# Digitizer.net
KiCad netlist of a schematic drawn in Altium Designer
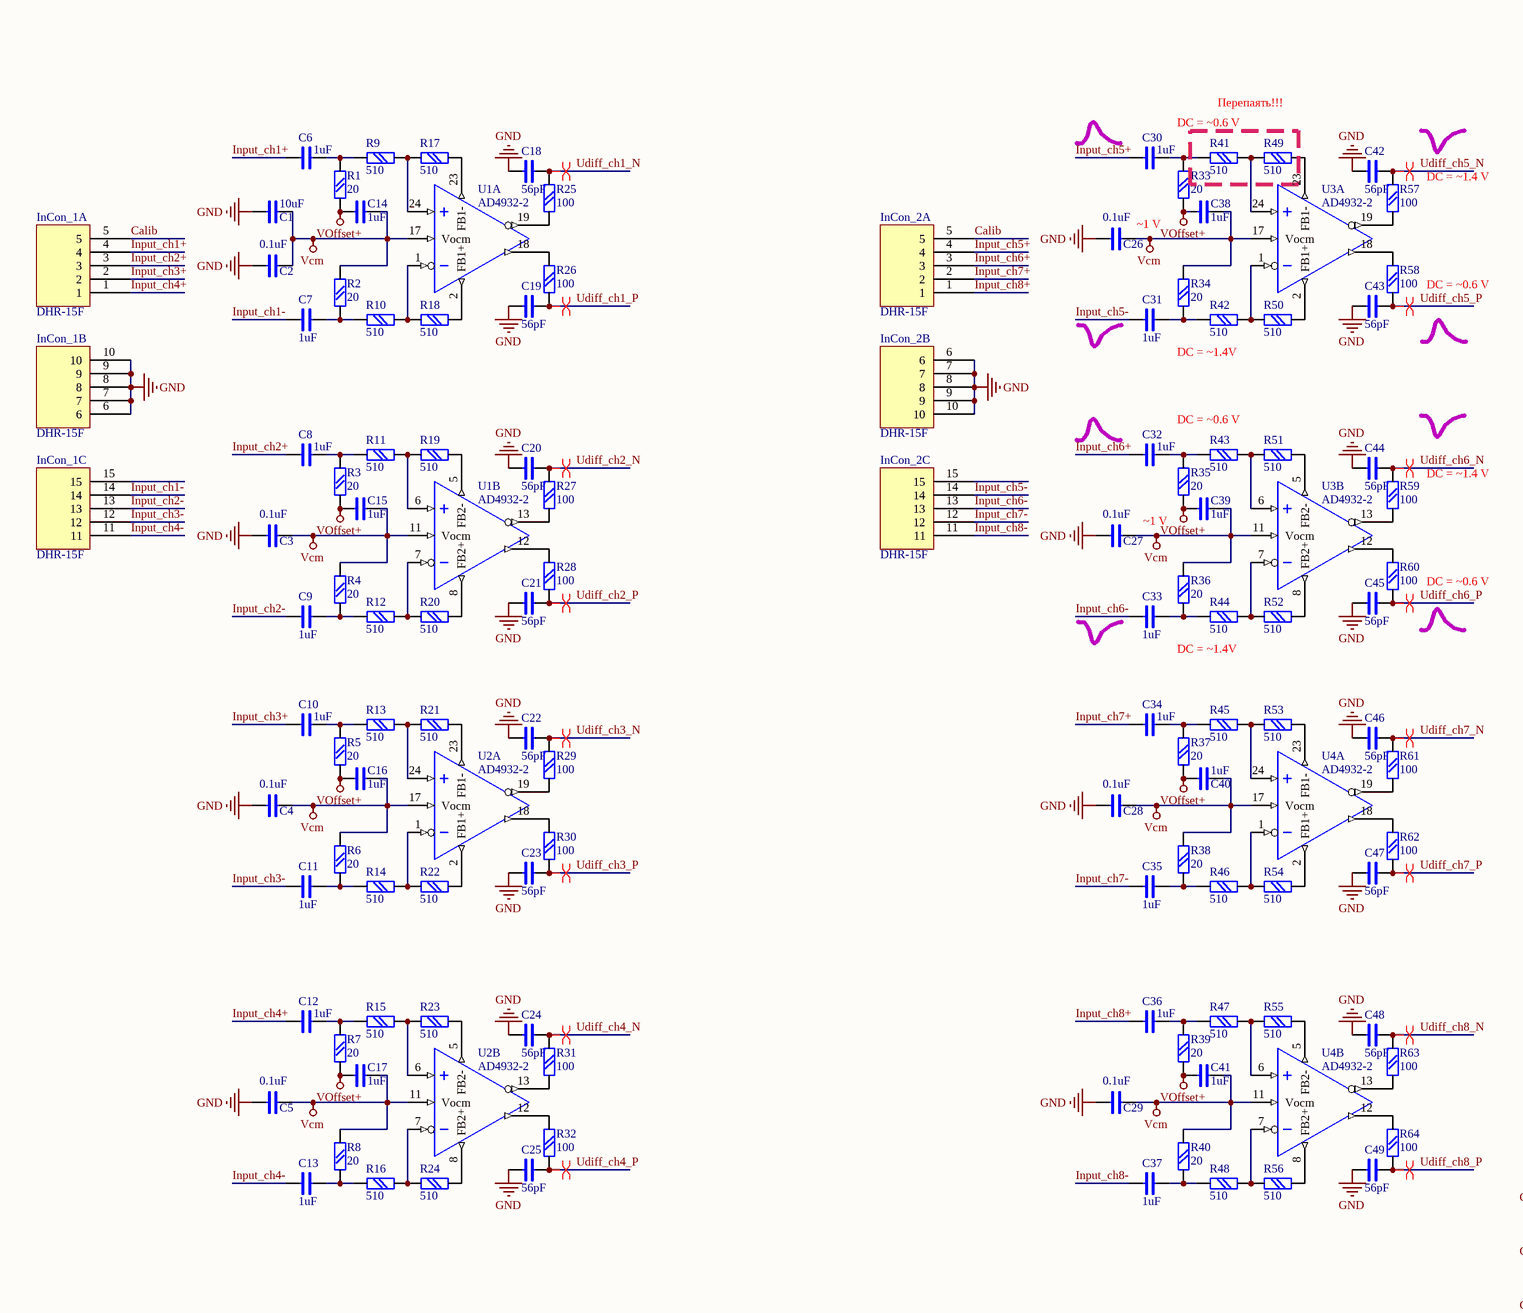
[diagram p0: Digitizer.SchDoc, left]
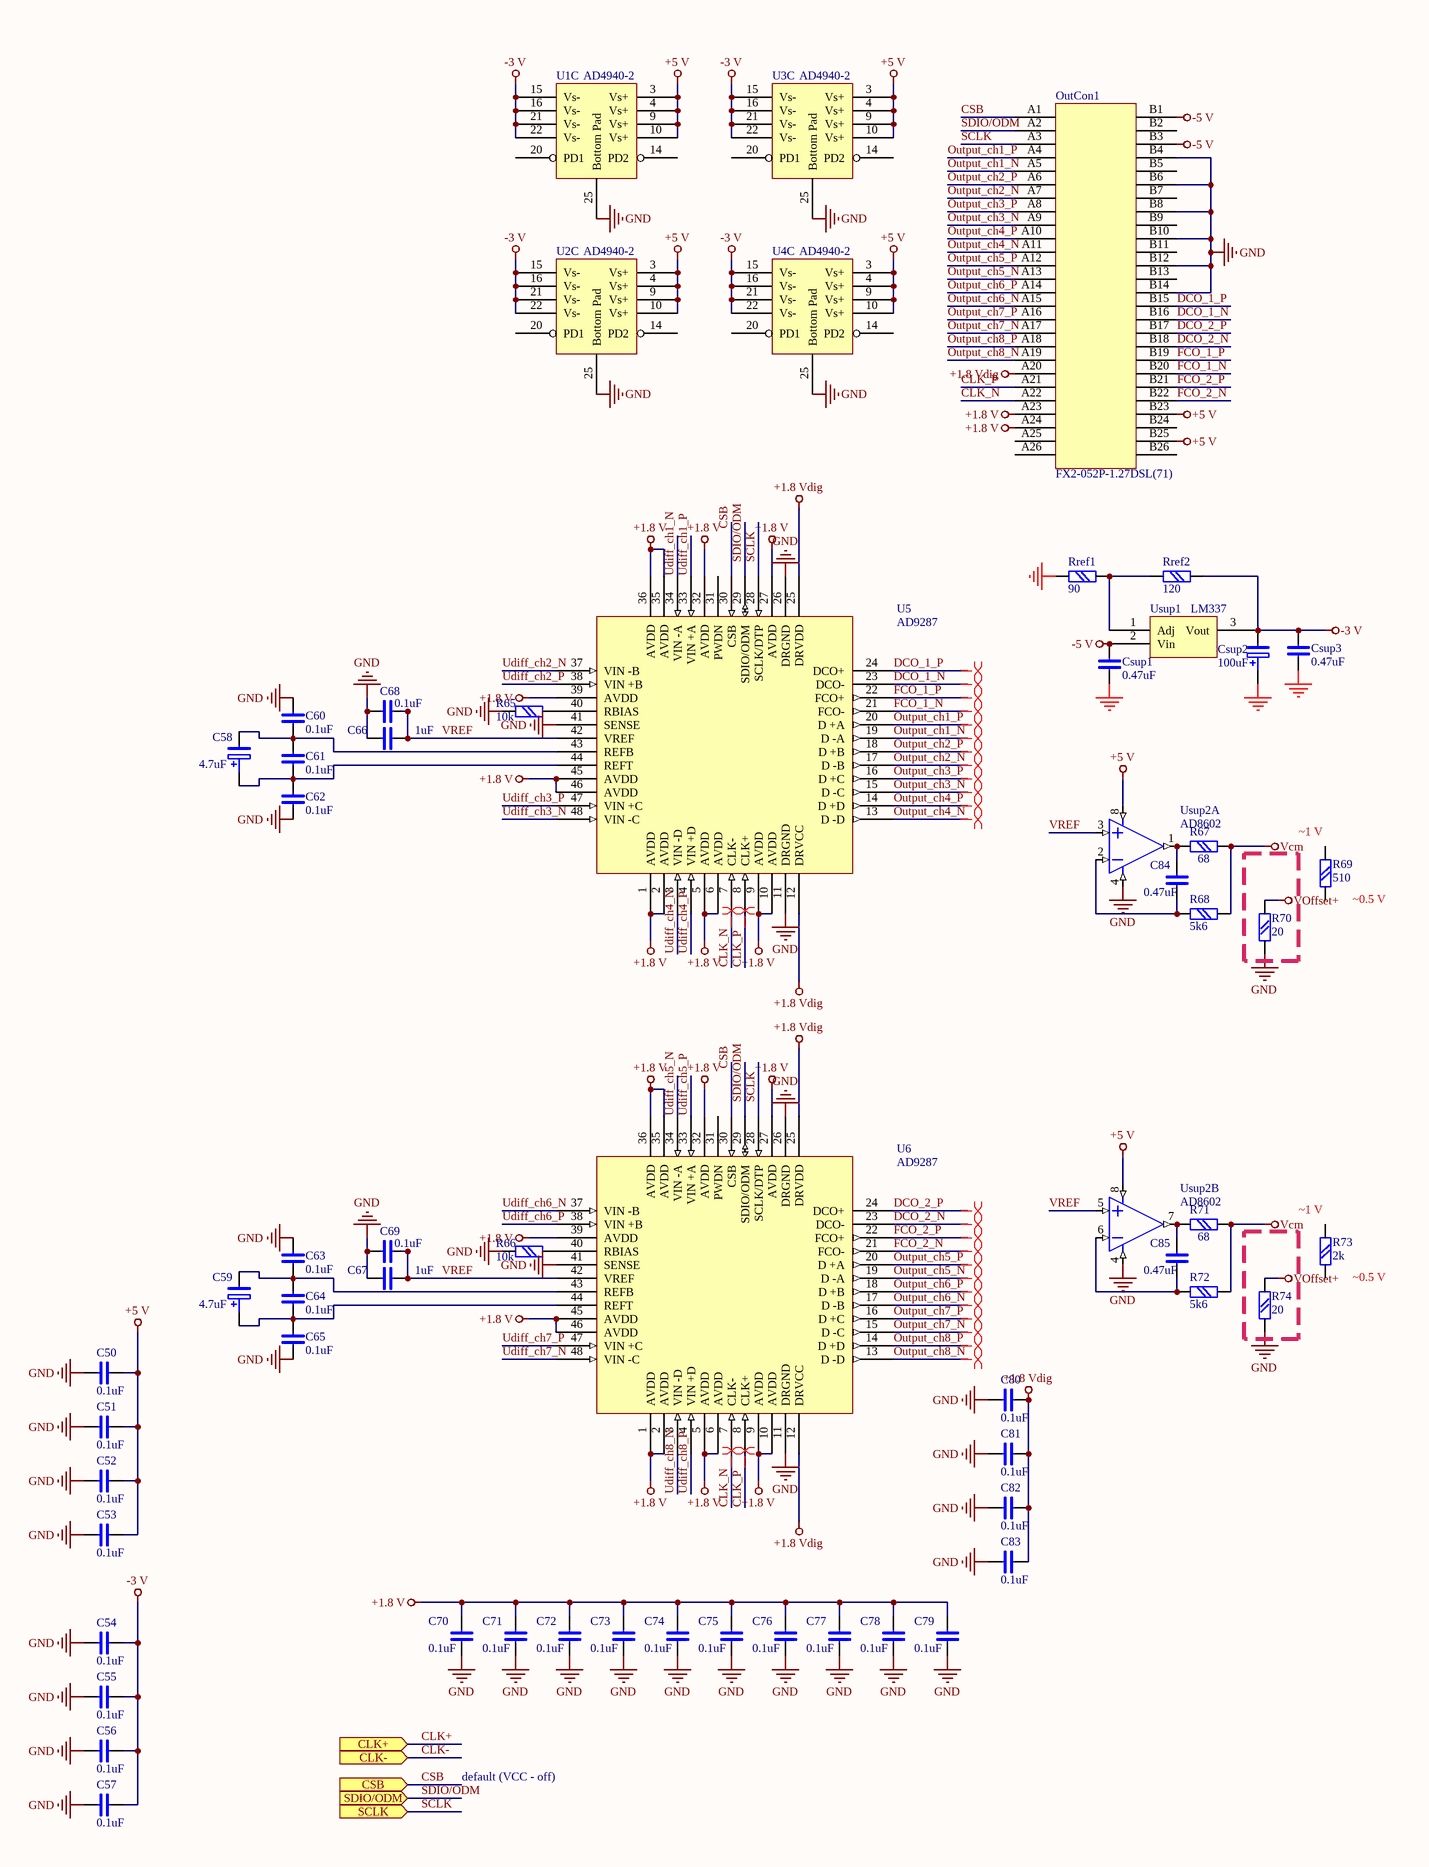
[diagram p1: Digitizer.SchDoc, right]

(export (version "E")
  (design (tool "Eeschema 10.0.6"))
  (components
    (comp (ref "C1") (value "10uF") (footprint "chip1206") (libsource (lib "vDevice") (part "C")))
    (comp (ref "C2") (value "0.1uF") (footprint "chip0603") (libsource (lib "vDevice") (part "C")))
    (comp (ref "C3") (value "0.1uF") (footprint "chip0603") (libsource (lib "vDevice") (part "C")))
    (comp (ref "C4") (value "0.1uF") (footprint "chip0603") (libsource (lib "vDevice") (part "C")))
    (comp (ref "C5") (value "0.1uF") (footprint "chip0603") (libsource (lib "vDevice") (part "C")))
    (comp (ref "C6") (value "1uF") (footprint "chip0603") (libsource (lib "vDevice") (part "C")))
    (comp (ref "C7") (value "1uF") (footprint "chip0603") (libsource (lib "vDevice") (part "C")))
    (comp (ref "C8") (value "1uF") (footprint "chip0603") (libsource (lib "vDevice") (part "C")))
    (comp (ref "C9") (value "1uF") (footprint "chip0603") (libsource (lib "vDevice") (part "C")))
    (comp (ref "C10") (value "1uF") (footprint "chip0603") (libsource (lib "vDevice") (part "C")))
    (comp (ref "C11") (value "1uF") (footprint "chip0603") (libsource (lib "vDevice") (part "C")))
    (comp (ref "C12") (value "1uF") (footprint "chip0603") (libsource (lib "vDevice") (part "C")))
    (comp (ref "C13") (value "1uF") (footprint "chip0603") (libsource (lib "vDevice") (part "C")))
    (comp (ref "C14") (value "1uF") (footprint "chip0603") (libsource (lib "vDevice") (part "C")))
    (comp (ref "C15") (value "1uF") (footprint "chip0603") (libsource (lib "vDevice") (part "C")))
    (comp (ref "C16") (value "1uF") (footprint "chip0603") (libsource (lib "vDevice") (part "C")))
    (comp (ref "C17") (value "1uF") (footprint "chip0603") (libsource (lib "vDevice") (part "C")))
    (comp (ref "C18") (value "56pF") (footprint "chip0603") (libsource (lib "vDevice") (part "C")))
    (comp (ref "C19") (value "56pF") (footprint "chip0603") (libsource (lib "vDevice") (part "C")))
    (comp (ref "C20") (value "56pF") (footprint "chip0603") (libsource (lib "vDevice") (part "C")))
    (comp (ref "C21") (value "56pF") (footprint "chip0603") (libsource (lib "vDevice") (part "C")))
    (comp (ref "C22") (value "56pF") (footprint "chip0603") (libsource (lib "vDevice") (part "C")))
    (comp (ref "C23") (value "56pF") (footprint "chip0603") (libsource (lib "vDevice") (part "C")))
    (comp (ref "C24") (value "56pF") (footprint "chip0603") (libsource (lib "vDevice") (part "C")))
    (comp (ref "C25") (value "56pF") (footprint "chip0603") (libsource (lib "vDevice") (part "C")))
    (comp (ref "C26") (value "0.1uF") (footprint "chip0603") (libsource (lib "vDevice") (part "C")))
    (comp (ref "C27") (value "0.1uF") (footprint "chip0603") (libsource (lib "vDevice") (part "C")))
    (comp (ref "C28") (value "0.1uF") (footprint "chip0603") (libsource (lib "vDevice") (part "C")))
    (comp (ref "C29") (value "0.1uF") (footprint "chip0603") (libsource (lib "vDevice") (part "C")))
    (comp (ref "C30") (value "1uF") (footprint "chip0603") (libsource (lib "vDevice") (part "C")))
    (comp (ref "C31") (value "1uF") (footprint "chip0603") (libsource (lib "vDevice") (part "C")))
    (comp (ref "C32") (value "1uF") (footprint "chip0603") (libsource (lib "vDevice") (part "C")))
    (comp (ref "C33") (value "1uF") (footprint "chip0603") (libsource (lib "vDevice") (part "C")))
    (comp (ref "C34") (value "1uF") (footprint "chip0603") (libsource (lib "vDevice") (part "C")))
    (comp (ref "C35") (value "1uF") (footprint "chip0603") (libsource (lib "vDevice") (part "C")))
    (comp (ref "C36") (value "1uF") (footprint "chip0603") (libsource (lib "vDevice") (part "C")))
    (comp (ref "C37") (value "1uF") (footprint "chip0603") (libsource (lib "vDevice") (part "C")))
    (comp (ref "C38") (value "1uF") (footprint "chip0603") (libsource (lib "vDevice") (part "C")))
    (comp (ref "C39") (value "1uF") (footprint "chip0603") (libsource (lib "vDevice") (part "C")))
    (comp (ref "C40") (value "1uF") (footprint "chip0603") (libsource (lib "vDevice") (part "C")))
    (comp (ref "C41") (value "1uF") (footprint "chip0603") (libsource (lib "vDevice") (part "C")))
    (comp (ref "C42") (value "56pF") (footprint "chip0603") (libsource (lib "vDevice") (part "C")))
    (comp (ref "C43") (value "56pF") (footprint "chip0603") (libsource (lib "vDevice") (part "C")))
    (comp (ref "C44") (value "56pF") (footprint "chip0603") (libsource (lib "vDevice") (part "C")))
    (comp (ref "C45") (value "56pF") (footprint "chip0603") (libsource (lib "vDevice") (part "C")))
    (comp (ref "C46") (value "56pF") (footprint "chip0603") (libsource (lib "vDevice") (part "C")))
    (comp (ref "C47") (value "56pF") (footprint "chip0603") (libsource (lib "vDevice") (part "C")))
    (comp (ref "C48") (value "56pF") (footprint "chip0603") (libsource (lib "vDevice") (part "C")))
    (comp (ref "C49") (value "56pF") (footprint "chip0603") (libsource (lib "vDevice") (part "C")))
    (comp (ref "C50") (value "0.1uF") (footprint "chip0603") (libsource (lib "vDevice") (part "C")))
    (comp (ref "C51") (value "0.1uF") (footprint "chip0603") (libsource (lib "vDevice") (part "C")))
    (comp (ref "C52") (value "0.1uF") (footprint "chip0603") (libsource (lib "vDevice") (part "C")))
    (comp (ref "C53") (value "0.1uF") (footprint "chip0603") (libsource (lib "vDevice") (part "C")))
    (comp (ref "C54") (value "0.1uF") (footprint "chip0603") (libsource (lib "vDevice") (part "C")))
    (comp (ref "C55") (value "0.1uF") (footprint "chip0603") (libsource (lib "vDevice") (part "C")))
    (comp (ref "C56") (value "0.1uF") (footprint "chip0603") (libsource (lib "vDevice") (part "C")))
    (comp (ref "C57") (value "0.1uF") (footprint "chip0603") (libsource (lib "vDevice") (part "C")))
    (comp (ref "C58") (value "4.7uF") (footprint "chip1206") (libsource (lib "vDevice") (part "C POL")))
    (comp (ref "C59") (value "4.7uF") (footprint "CHIP1206") (libsource (lib "vDevice") (part "C POL")))
    (comp (ref "C60") (value "0.1uF") (footprint "chip0603") (libsource (lib "vDevice") (part "C")))
    (comp (ref "C61") (value "0.1uF") (footprint "chip0603") (libsource (lib "vDevice") (part "C")))
    (comp (ref "C62") (value "0.1uF") (footprint "chip0603") (libsource (lib "vDevice") (part "C")))
    (comp (ref "C63") (value "0.1uF") (footprint "chip0603") (libsource (lib "vDevice") (part "C")))
    (comp (ref "C64") (value "0.1uF") (footprint "chip0603") (libsource (lib "vDevice") (part "C")))
    (comp (ref "C65") (value "0.1uF") (footprint "chip0603") (libsource (lib "vDevice") (part "C")))
    (comp (ref "C66") (value "1uF") (footprint "chip0603") (libsource (lib "vDevice") (part "C")))
    (comp (ref "C67") (value "1uF") (footprint "chip0603") (libsource (lib "vDevice") (part "C")))
    (comp (ref "C68") (value "0.1uF") (footprint "chip0603") (libsource (lib "vDevice") (part "C")))
    (comp (ref "C69") (value "0.1uF") (footprint "chip0603") (libsource (lib "vDevice") (part "C")))
    (comp (ref "C70") (value "0.1uF") (footprint "chip0603") (libsource (lib "vDevice") (part "C")))
    (comp (ref "C71") (value "0.1uF") (footprint "chip0603") (libsource (lib "vDevice") (part "C")))
    (comp (ref "C72") (value "0.1uF") (footprint "chip0603") (libsource (lib "vDevice") (part "C")))
    (comp (ref "C73") (value "0.1uF") (footprint "chip0603") (libsource (lib "vDevice") (part "C")))
    (comp (ref "C74") (value "0.1uF") (footprint "chip0603") (libsource (lib "vDevice") (part "C")))
    (comp (ref "C75") (value "0.1uF") (footprint "chip0603") (libsource (lib "vDevice") (part "C")))
    (comp (ref "C76") (value "0.1uF") (footprint "chip0603") (libsource (lib "vDevice") (part "C")))
    (comp (ref "C77") (value "0.1uF") (footprint "chip0603") (libsource (lib "vDevice") (part "C")))
    (comp (ref "C78") (value "0.1uF") (footprint "chip0603") (libsource (lib "vDevice") (part "C")))
    (comp (ref "C79") (value "0.1uF") (footprint "chip0603") (libsource (lib "vDevice") (part "C")))
    (comp (ref "C80") (value "0.1uF") (footprint "chip0603") (libsource (lib "vDevice") (part "C")))
    (comp (ref "C81") (value "0.1uF") (footprint "chip0603") (libsource (lib "vDevice") (part "C")))
    (comp (ref "C82") (value "0.1uF") (footprint "chip0603") (libsource (lib "vDevice") (part "C")))
    (comp (ref "C83") (value "0.1uF") (footprint "chip0603") (libsource (lib "vDevice") (part "C")))
    (comp (ref "C84") (value "0.47uF") (footprint "chip0603") (libsource (lib "*") (part "C")))
    (comp (ref "C85") (value "0.47uF") (footprint "chip0603") (libsource (lib "*") (part "C")))
    (comp (ref "Csup1") (value "0.47uF") (footprint "chip0603") (libsource (lib "*") (part "C")))
    (comp (ref "Csup2") (value "100uF") (footprint "CEL-SMD300") (libsource (lib "*") (part "C POL")))
    (comp (ref "Csup3") (value "0.47uF") (footprint "chip0603") (libsource (lib "*") (part "C")))
    (comp (ref "InCon_1")
      (value "DHR-15F")
      (footprint "DHR-F-15")
      (libsource (lib "vDevice") (part "DHR-15F"))
    )
    (comp (ref "InCon_2")
      (value "DHR-15F")
      (footprint "DHR-F-15")
      (libsource (lib "vDevice") (part "DHR-15F"))
    )
    (comp (ref "OutCon1")
      (value "FX2-052P-1.27DSL(71)")
      (footprint "FX2-52P-1.27DSL(71)")
      (libsource (lib "vDevice") (part "FX2-052P-1.27DSL(71)"))
    )
    (comp (ref "R1") (value "20") (footprint "chip0603") (libsource (lib "vDevice") (part "R")))
    (comp (ref "R2") (value "20") (footprint "chip0603") (libsource (lib "vDevice") (part "R")))
    (comp (ref "R3") (value "20") (footprint "chip0603") (libsource (lib "vDevice") (part "R")))
    (comp (ref "R4") (value "20") (footprint "chip0603") (libsource (lib "vDevice") (part "R")))
    (comp (ref "R5") (value "20") (footprint "chip0603") (libsource (lib "vDevice") (part "R")))
    (comp (ref "R6") (value "20") (footprint "chip0603") (libsource (lib "vDevice") (part "R")))
    (comp (ref "R7") (value "20") (footprint "chip0603") (libsource (lib "vDevice") (part "R")))
    (comp (ref "R8") (value "20") (footprint "chip0603") (libsource (lib "vDevice") (part "R")))
    (comp (ref "R9") (value "510") (footprint "chip0603") (libsource (lib "vDevice") (part "R")))
    (comp (ref "R10") (value "510") (footprint "chip0603") (libsource (lib "vDevice") (part "R")))
    (comp (ref "R11") (value "510") (footprint "chip0603") (libsource (lib "vDevice") (part "R")))
    (comp (ref "R12") (value "510") (footprint "chip0603") (libsource (lib "vDevice") (part "R")))
    (comp (ref "R13") (value "510") (footprint "chip0603") (libsource (lib "vDevice") (part "R")))
    (comp (ref "R14") (value "510") (footprint "chip0603") (libsource (lib "vDevice") (part "R")))
    (comp (ref "R15") (value "510") (footprint "chip0603") (libsource (lib "vDevice") (part "R")))
    (comp (ref "R16") (value "510") (footprint "chip0603") (libsource (lib "vDevice") (part "R")))
    (comp (ref "R17") (value "510") (footprint "chip0603") (libsource (lib "vDevice") (part "R")))
    (comp (ref "R18") (value "510") (footprint "chip0603") (libsource (lib "vDevice") (part "R")))
    (comp (ref "R19") (value "510") (footprint "chip0603") (libsource (lib "vDevice") (part "R")))
    (comp (ref "R20") (value "510") (footprint "chip0603") (libsource (lib "vDevice") (part "R")))
    (comp (ref "R21") (value "510") (footprint "chip0603") (libsource (lib "vDevice") (part "R")))
    (comp (ref "R22") (value "510") (footprint "chip0603") (libsource (lib "vDevice") (part "R")))
    (comp (ref "R23") (value "510") (footprint "chip0603") (libsource (lib "vDevice") (part "R")))
    (comp (ref "R24") (value "510") (footprint "chip0603") (libsource (lib "vDevice") (part "R")))
    (comp (ref "R25") (value "100") (footprint "chip0603") (libsource (lib "vDevice") (part "R")))
    (comp (ref "R26") (value "100") (footprint "chip0603") (libsource (lib "vDevice") (part "R")))
    (comp (ref "R27") (value "100") (footprint "chip0603") (libsource (lib "vDevice") (part "R")))
    (comp (ref "R28") (value "100") (footprint "chip0603") (libsource (lib "vDevice") (part "R")))
    (comp (ref "R29") (value "100") (footprint "chip0603") (libsource (lib "vDevice") (part "R")))
    (comp (ref "R30") (value "100") (footprint "chip0603") (libsource (lib "vDevice") (part "R")))
    (comp (ref "R31") (value "100") (footprint "chip0603") (libsource (lib "vDevice") (part "R")))
    (comp (ref "R32") (value "100") (footprint "chip0603") (libsource (lib "vDevice") (part "R")))
    (comp (ref "R33") (value "20") (footprint "chip0603") (libsource (lib "vDevice") (part "R")))
    (comp (ref "R34") (value "20") (footprint "chip0603") (libsource (lib "vDevice") (part "R")))
    (comp (ref "R35") (value "20") (footprint "chip0603") (libsource (lib "vDevice") (part "R")))
    (comp (ref "R36") (value "20") (footprint "chip0603") (libsource (lib "vDevice") (part "R")))
    (comp (ref "R37") (value "20") (footprint "chip0603") (libsource (lib "vDevice") (part "R")))
    (comp (ref "R38") (value "20") (footprint "chip0603") (libsource (lib "vDevice") (part "R")))
    (comp (ref "R39") (value "20") (footprint "chip0603") (libsource (lib "vDevice") (part "R")))
    (comp (ref "R40") (value "20") (footprint "chip0603") (libsource (lib "vDevice") (part "R")))
    (comp (ref "R41") (value "510") (footprint "chip0603") (libsource (lib "vDevice") (part "R")))
    (comp (ref "R42") (value "510") (footprint "chip0603") (libsource (lib "vDevice") (part "R")))
    (comp (ref "R43") (value "510") (footprint "chip0603") (libsource (lib "vDevice") (part "R")))
    (comp (ref "R44") (value "510") (footprint "chip0603") (libsource (lib "vDevice") (part "R")))
    (comp (ref "R45") (value "510") (footprint "chip0603") (libsource (lib "vDevice") (part "R")))
    (comp (ref "R46") (value "510") (footprint "chip0603") (libsource (lib "vDevice") (part "R")))
    (comp (ref "R47") (value "510") (footprint "chip0603") (libsource (lib "vDevice") (part "R")))
    (comp (ref "R48") (value "510") (footprint "chip0603") (libsource (lib "vDevice") (part "R")))
    (comp (ref "R49") (value "510") (footprint "chip0603") (libsource (lib "vDevice") (part "R")))
    (comp (ref "R50") (value "510") (footprint "chip0603") (libsource (lib "vDevice") (part "R")))
    (comp (ref "R51") (value "510") (footprint "chip0603") (libsource (lib "vDevice") (part "R")))
    (comp (ref "R52") (value "510") (footprint "chip0603") (libsource (lib "vDevice") (part "R")))
    (comp (ref "R53") (value "510") (footprint "chip0603") (libsource (lib "vDevice") (part "R")))
    (comp (ref "R54") (value "510") (footprint "chip0603") (libsource (lib "vDevice") (part "R")))
    (comp (ref "R55") (value "510") (footprint "chip0603") (libsource (lib "vDevice") (part "R")))
    (comp (ref "R56") (value "510") (footprint "chip0603") (libsource (lib "vDevice") (part "R")))
    (comp (ref "R57") (value "100") (footprint "chip0603") (libsource (lib "vDevice") (part "R")))
    (comp (ref "R58") (value "100") (footprint "chip0603") (libsource (lib "vDevice") (part "R")))
    (comp (ref "R59") (value "100") (footprint "chip0603") (libsource (lib "vDevice") (part "R")))
    (comp (ref "R60") (value "100") (footprint "chip0603") (libsource (lib "vDevice") (part "R")))
    (comp (ref "R61") (value "100") (footprint "chip0603") (libsource (lib "vDevice") (part "R")))
    (comp (ref "R62") (value "100") (footprint "chip0603") (libsource (lib "vDevice") (part "R")))
    (comp (ref "R63") (value "100") (footprint "chip0603") (libsource (lib "vDevice") (part "R")))
    (comp (ref "R64") (value "100") (footprint "chip0603") (libsource (lib "vDevice") (part "R")))
    (comp (ref "R65") (value "10k") (footprint "chip0603") (libsource (lib "vDevice") (part "R")))
    (comp (ref "R66") (value "10k") (footprint "chip0603") (libsource (lib "vDevice") (part "R")))
    (comp (ref "R67") (value "68") (footprint "chip0603") (libsource (lib "vDevice") (part "R")))
    (comp (ref "R68") (value "5k6") (footprint "chip0603") (libsource (lib "vDevice") (part "R")))
    (comp (ref "R69") (value "510") (footprint "chip0603") (libsource (lib "vDevice") (part "R")))
    (comp (ref "R70") (value "20") (footprint "chip0603") (libsource (lib "vDevice") (part "R")))
    (comp (ref "R71") (value "68") (footprint "chip0603") (libsource (lib "vDevice") (part "R")))
    (comp (ref "R72") (value "5k6") (footprint "chip0603") (libsource (lib "vDevice") (part "R")))
    (comp (ref "R73") (value "2k") (footprint "chip0603") (libsource (lib "vDevice") (part "R")))
    (comp (ref "R74") (value "20") (footprint "chip0603") (libsource (lib "vDevice") (part "R")))
    (comp (ref "Rref1") (value "90") (footprint "chip0603") (libsource (lib "*") (part "MLT")))
    (comp (ref "Rref2") (value "120") (footprint "chip0603") (libsource (lib "*") (part "MLT")))
    (comp (ref "U1")
      (value "AD4932-2")
      (footprint "CP-24-13")
      (libsource (lib "Backup of Mylib") (part "AD4932-2"))
    )
    (comp (ref "U2") (value "AD4932-2") (footprint "CP-24-13") (libsource (lib "") (part "AD4932-2_1")))
    (comp (ref "U3")
      (value "AD4932-2")
      (footprint "CP-24-13")
      (libsource (lib "Backup of Mylib") (part "AD4932-2"))
    )
    (comp (ref "U4") (value "AD4932-2") (footprint "CP-24-13") (libsource (lib "") (part "AD4932-2_1")))
    (comp (ref "U5")
      (value "AD9287")
      (footprint "CP-48-8")
      (libsource (lib "Backup of Mylib") (part "AD9287"))
    )
    (comp (ref "U6")
      (value "AD9287")
      (footprint "CP-48-8")
      (libsource (lib "Backup of Mylib") (part "AD9287"))
    )
    (comp (ref "Usup1")
      (value "LM337")
      (footprint "SOT223_N")
      (description "3-Terminal Adjustable Negative Regulators")
      (libsource (lib "Backup of Mylib") (part "LM337"))
    )
    (comp (ref "Usup2") (value "AD8602") (footprint "8SO200") (libsource (lib "vAnalog") (part "KR1040UD1")))
  )
  (nets
    (net (code "1") (name "+1.8 V") (class "Default")
      (node (ref "C70") (pin "2") (pinfunction "2_2") (pintype "passive"))
      (node (ref "C71") (pin "2") (pinfunction "2_2") (pintype "passive"))
      (node (ref "C72") (pin "2") (pinfunction "2_2") (pintype "passive"))
      (node (ref "C73") (pin "2") (pinfunction "2_2") (pintype "passive"))
      (node (ref "C74") (pin "2") (pinfunction "2_2") (pintype "passive"))
      (node (ref "C75") (pin "2") (pinfunction "2_2") (pintype "passive"))
      (node (ref "C76") (pin "2") (pinfunction "2_2") (pintype "passive"))
      (node (ref "C77") (pin "2") (pinfunction "2_2") (pintype "passive"))
      (node (ref "C78") (pin "2") (pinfunction "2_2") (pintype "passive"))
      (node (ref "C79") (pin "2") (pinfunction "2_2") (pintype "passive"))
      (node (ref "OutCon1") (pin "A23") (pinfunction "A23_A23") (pintype "passive"))
      (node (ref "OutCon1") (pin "A24") (pinfunction "A24_A24") (pintype "passive"))
      (node (ref "U5") (pin "1") (pinfunction "AVDD_1") (pintype "passive"))
      (node (ref "U5") (pin "10") (pinfunction "AVDD_10") (pintype "power_in"))
      (node (ref "U5") (pin "2") (pinfunction "AVDD_2") (pintype "power_in"))
      (node (ref "U5") (pin "27") (pinfunction "AVDD_27") (pintype "power_in"))
      (node (ref "U5") (pin "32") (pinfunction "AVDD_32") (pintype "power_in"))
      (node (ref "U5") (pin "35") (pinfunction "AVDD_35") (pintype "power_in"))
      (node (ref "U5") (pin "36") (pinfunction "AVDD_36") (pintype "power_in"))
      (node (ref "U5") (pin "39") (pinfunction "AVDD_39") (pintype "power_in"))
      (node (ref "U5") (pin "45") (pinfunction "AVDD_45") (pintype "passive"))
      (node (ref "U5") (pin "46") (pinfunction "AVDD_46") (pintype "power_in"))
      (node (ref "U5") (pin "5") (pinfunction "AVDD_5") (pintype "power_in"))
      (node (ref "U5") (pin "6") (pinfunction "AVDD_6") (pintype "power_in"))
      (node (ref "U5") (pin "9") (pinfunction "AVDD_9") (pintype "power_in"))
      (node (ref "U6") (pin "1") (pinfunction "AVDD_1") (pintype "passive"))
      (node (ref "U6") (pin "10") (pinfunction "AVDD_10") (pintype "power_in"))
      (node (ref "U6") (pin "2") (pinfunction "AVDD_2") (pintype "power_in"))
      (node (ref "U6") (pin "27") (pinfunction "AVDD_27") (pintype "power_in"))
      (node (ref "U6") (pin "32") (pinfunction "AVDD_32") (pintype "power_in"))
      (node (ref "U6") (pin "35") (pinfunction "AVDD_35") (pintype "power_in"))
      (node (ref "U6") (pin "36") (pinfunction "AVDD_36") (pintype "power_in"))
      (node (ref "U6") (pin "39") (pinfunction "AVDD_39") (pintype "power_in"))
      (node (ref "U6") (pin "45") (pinfunction "AVDD_45") (pintype "passive"))
      (node (ref "U6") (pin "46") (pinfunction "AVDD_46") (pintype "power_in"))
      (node (ref "U6") (pin "5") (pinfunction "AVDD_5") (pintype "power_in"))
      (node (ref "U6") (pin "6") (pinfunction "AVDD_6") (pintype "power_in"))
      (node (ref "U6") (pin "9") (pinfunction "AVDD_9") (pintype "power_in"))
    )
    (net (code "2") (name "+1.8 Vdig") (class "Default")
      (node (ref "C80") (pin "2") (pinfunction "2_2") (pintype "passive"))
      (node (ref "C81") (pin "2") (pinfunction "2_2") (pintype "passive"))
      (node (ref "C82") (pin "2") (pinfunction "2_2") (pintype "passive"))
      (node (ref "C83") (pin "2") (pinfunction "2_2") (pintype "passive"))
      (node (ref "OutCon1") (pin "A20") (pinfunction "20_A20") (pintype "passive"))
      (node (ref "U5") (pin "12") (pinfunction "DRVCC_12") (pintype "power_in"))
      (node (ref "U5") (pin "25") (pinfunction "DRVDD_25") (pintype "power_in"))
      (node (ref "U6") (pin "12") (pinfunction "DRVCC_12") (pintype "power_in"))
      (node (ref "U6") (pin "25") (pinfunction "DRVDD_25") (pintype "power_in"))
    )
    (net (code "3") (name "+5 V") (class "Default")
      (node (ref "C50") (pin "2") (pinfunction "2_2") (pintype "passive"))
      (node (ref "C51") (pin "2") (pinfunction "2_2") (pintype "passive"))
      (node (ref "C52") (pin "2") (pinfunction "2_2") (pintype "passive"))
      (node (ref "C53") (pin "2") (pinfunction "2_2") (pintype "passive"))
      (node (ref "OutCon1") (pin "B23") (pinfunction "B23_B23") (pintype "passive"))
      (node (ref "OutCon1") (pin "B25") (pinfunction "B25_B25") (pintype "passive"))
      (node (ref "U1") (pin "10") (pinfunction "Vs+_10") (pintype "power_in"))
      (node (ref "U1") (pin "3") (pinfunction "Vs+_3") (pintype "power_in"))
      (node (ref "U1") (pin "4") (pinfunction "Vs+_4") (pintype "power_in"))
      (node (ref "U1") (pin "9") (pinfunction "Vs+_9") (pintype "power_in"))
      (node (ref "U2") (pin "10") (pinfunction "Vs+_10") (pintype "power_in"))
      (node (ref "U2") (pin "3") (pinfunction "Vs+_3") (pintype "power_in"))
      (node (ref "U2") (pin "4") (pinfunction "Vs+_4") (pintype "power_in"))
      (node (ref "U2") (pin "9") (pinfunction "Vs+_9") (pintype "power_in"))
      (node (ref "U3") (pin "10") (pinfunction "Vs+_10") (pintype "power_in"))
      (node (ref "U3") (pin "3") (pinfunction "Vs+_3") (pintype "power_in"))
      (node (ref "U3") (pin "4") (pinfunction "Vs+_4") (pintype "power_in"))
      (node (ref "U3") (pin "9") (pinfunction "Vs+_9") (pintype "power_in"))
      (node (ref "U4") (pin "10") (pinfunction "Vs+_10") (pintype "power_in"))
      (node (ref "U4") (pin "3") (pinfunction "Vs+_3") (pintype "power_in"))
      (node (ref "U4") (pin "4") (pinfunction "Vs+_4") (pintype "power_in"))
      (node (ref "U4") (pin "9") (pinfunction "Vs+_9") (pintype "power_in"))
      (node (ref "Usup2") (pin "8") (pinfunction "E+_8") (pintype "input"))
    )
    (net (code "4") (name "-3 V") (class "Default")
      (node (ref "C54") (pin "2") (pinfunction "2_2") (pintype "passive"))
      (node (ref "C55") (pin "2") (pinfunction "2_2") (pintype "passive"))
      (node (ref "C56") (pin "2") (pinfunction "2_2") (pintype "passive"))
      (node (ref "C57") (pin "2") (pinfunction "2_2") (pintype "passive"))
      (node (ref "Csup2") (pin "-") (pinfunction "-_-") (pintype "passive"))
      (node (ref "Csup3") (pin "1") (pinfunction "1_1") (pintype "passive"))
      (node (ref "Rref2") (pin "1") (pinfunction "1_1") (pintype "passive"))
      (node (ref "U1") (pin "15") (pinfunction "Vs-_15") (pintype "power_in"))
      (node (ref "U1") (pin "16") (pinfunction "Vs-_16") (pintype "power_in"))
      (node (ref "U1") (pin "21") (pinfunction "Vs-_21") (pintype "power_in"))
      (node (ref "U1") (pin "22") (pinfunction "Vs-_22") (pintype "power_in"))
      (node (ref "U2") (pin "15") (pinfunction "Vs-_15") (pintype "power_in"))
      (node (ref "U2") (pin "16") (pinfunction "Vs-_16") (pintype "power_in"))
      (node (ref "U2") (pin "21") (pinfunction "Vs-_21") (pintype "power_in"))
      (node (ref "U2") (pin "22") (pinfunction "Vs-_22") (pintype "power_in"))
      (node (ref "U3") (pin "15") (pinfunction "Vs-_15") (pintype "power_in"))
      (node (ref "U3") (pin "16") (pinfunction "Vs-_16") (pintype "power_in"))
      (node (ref "U3") (pin "21") (pinfunction "Vs-_21") (pintype "power_in"))
      (node (ref "U3") (pin "22") (pinfunction "Vs-_22") (pintype "power_in"))
      (node (ref "U4") (pin "15") (pinfunction "Vs-_15") (pintype "power_in"))
      (node (ref "U4") (pin "16") (pinfunction "Vs-_16") (pintype "power_in"))
      (node (ref "U4") (pin "21") (pinfunction "Vs-_21") (pintype "power_in"))
      (node (ref "U4") (pin "22") (pinfunction "Vs-_22") (pintype "power_in"))
      (node (ref "Usup1") (pin "3") (pinfunction "Vout_3") (pintype "passive"))
    )
    (net (code "5") (name "-5 V") (class "Default")
      (node (ref "Csup1") (pin "1") (pinfunction "1_1") (pintype "passive"))
      (node (ref "OutCon1") (pin "B1") (pinfunction "1_B1") (pintype "passive"))
      (node (ref "OutCon1") (pin "B3") (pinfunction "3_B3") (pintype "passive"))
      (node (ref "Usup1") (pin "2") (pinfunction "Vin_2") (pintype "passive"))
    )
    (net (code "8") (name "/CLK_N") (class "Default")
      (node (ref "OutCon1") (pin "A22") (pinfunction "A22_A22") (pintype "passive"))
      (node (ref "U5") (pin "7") (pinfunction "CLK-_7") (pintype "input"))
      (node (ref "U6") (pin "7") (pinfunction "CLK-_7") (pintype "input"))
    )
    (net (code "9") (name "/CLK_P") (class "Default")
      (node (ref "OutCon1") (pin "A21") (pinfunction "A21_A21") (pintype "passive"))
      (node (ref "U5") (pin "8") (pinfunction "CLK+_8") (pintype "input"))
      (node (ref "U6") (pin "8") (pinfunction "CLK+_8") (pintype "input"))
    )
    (net (code "10") (name "/CSB") (class "Default")
      (node (ref "OutCon1") (pin "A1") (pinfunction "1_A1") (pintype "passive"))
      (node (ref "U5") (pin "30") (pinfunction "CSB_30") (pintype "input"))
      (node (ref "U6") (pin "30") (pinfunction "CSB_30") (pintype "input"))
    )
    (net (code "11") (name "/Calib") (class "Default")
      (node (ref "InCon_1") (pin "5") (pinfunction "5_5") (pintype "passive"))
      (node (ref "InCon_2") (pin "5") (pinfunction "5_5") (pintype "passive"))
    )
    (net (code "12") (name "/DCO_1_N") (class "Default")
      (node (ref "OutCon1") (pin "B16") (pinfunction "16_B16") (pintype "passive"))
      (node (ref "U5") (pin "23") (pinfunction "DCO-_23") (pintype "passive"))
    )
    (net (code "13") (name "/DCO_1_P") (class "Default")
      (node (ref "OutCon1") (pin "B15") (pinfunction "15_B15") (pintype "passive"))
      (node (ref "U5") (pin "24") (pinfunction "DCO+_24") (pintype "passive"))
    )
    (net (code "14") (name "/DCO_2_N") (class "Default")
      (node (ref "OutCon1") (pin "B18") (pinfunction "18_B18") (pintype "passive"))
      (node (ref "U6") (pin "23") (pinfunction "DCO-_23") (pintype "passive"))
    )
    (net (code "15") (name "/DCO_2_P") (class "Default")
      (node (ref "OutCon1") (pin "B17") (pinfunction "17_B17") (pintype "passive"))
      (node (ref "U6") (pin "24") (pinfunction "DCO+_24") (pintype "passive"))
    )
    (net (code "16") (name "/FCO_1_N") (class "Default")
      (node (ref "OutCon1") (pin "B20") (pinfunction "20_B20") (pintype "passive"))
      (node (ref "U5") (pin "21") (pinfunction "FCO-_21") (pintype "output"))
    )
    (net (code "17") (name "/FCO_1_P") (class "Default")
      (node (ref "OutCon1") (pin "B19") (pinfunction "19_B19") (pintype "passive"))
      (node (ref "U5") (pin "22") (pinfunction "FCO+_22") (pintype "output"))
    )
    (net (code "18") (name "/FCO_2_N") (class "Default")
      (node (ref "OutCon1") (pin "B22") (pinfunction "B22_B22") (pintype "passive"))
      (node (ref "U6") (pin "21") (pinfunction "FCO-_21") (pintype "output"))
    )
    (net (code "19") (name "/FCO_2_P") (class "Default")
      (node (ref "OutCon1") (pin "B21") (pinfunction "B21_B21") (pintype "passive"))
      (node (ref "U6") (pin "22") (pinfunction "FCO+_22") (pintype "output"))
    )
    (net (code "20") (name "/Input_ch1+") (class "Default")
      (node (ref "C6") (pin "1") (pinfunction "1_1") (pintype "passive"))
      (node (ref "InCon_1") (pin "4") (pinfunction "4_4") (pintype "passive"))
    )
    (net (code "21") (name "/Input_ch1-") (class "Default")
      (node (ref "C7") (pin "1") (pinfunction "1_1") (pintype "passive"))
      (node (ref "InCon_1") (pin "14") (pinfunction "14_14") (pintype "passive"))
    )
    (net (code "22") (name "/Input_ch2+") (class "Default")
      (node (ref "C8") (pin "1") (pinfunction "1_1") (pintype "passive"))
      (node (ref "InCon_1") (pin "3") (pinfunction "3_3") (pintype "passive"))
    )
    (net (code "23") (name "/Input_ch2-") (class "Default")
      (node (ref "C9") (pin "1") (pinfunction "1_1") (pintype "passive"))
      (node (ref "InCon_1") (pin "13") (pinfunction "13_13") (pintype "passive"))
    )
    (net (code "24") (name "/Input_ch3+") (class "Default")
      (node (ref "C10") (pin "1") (pinfunction "1_1") (pintype "passive"))
      (node (ref "InCon_1") (pin "2") (pinfunction "2_2") (pintype "passive"))
    )
    (net (code "25") (name "/Input_ch3-") (class "Default")
      (node (ref "C11") (pin "1") (pinfunction "1_1") (pintype "passive"))
      (node (ref "InCon_1") (pin "12") (pinfunction "12_12") (pintype "passive"))
    )
    (net (code "26") (name "/Input_ch4+") (class "Default")
      (node (ref "C12") (pin "1") (pinfunction "1_1") (pintype "passive"))
      (node (ref "InCon_1") (pin "1") (pinfunction "1_1") (pintype "passive"))
    )
    (net (code "27") (name "/Input_ch4-") (class "Default")
      (node (ref "C13") (pin "1") (pinfunction "1_1") (pintype "passive"))
      (node (ref "InCon_1") (pin "11") (pinfunction "11_11") (pintype "passive"))
    )
    (net (code "28") (name "/Input_ch5+") (class "Default")
      (node (ref "C30") (pin "1") (pinfunction "1_1") (pintype "passive"))
      (node (ref "InCon_2") (pin "4") (pinfunction "4_4") (pintype "passive"))
    )
    (net (code "29") (name "/Input_ch5-") (class "Default")
      (node (ref "C31") (pin "1") (pinfunction "1_1") (pintype "passive"))
      (node (ref "InCon_2") (pin "14") (pinfunction "14_14") (pintype "passive"))
    )
    (net (code "30") (name "/Input_ch6+") (class "Default")
      (node (ref "C32") (pin "1") (pinfunction "1_1") (pintype "passive"))
      (node (ref "InCon_2") (pin "3") (pinfunction "3_3") (pintype "passive"))
    )
    (net (code "31") (name "/Input_ch6-") (class "Default")
      (node (ref "C33") (pin "1") (pinfunction "1_1") (pintype "passive"))
      (node (ref "InCon_2") (pin "13") (pinfunction "13_13") (pintype "passive"))
    )
    (net (code "32") (name "/Input_ch7+") (class "Default")
      (node (ref "C34") (pin "1") (pinfunction "1_1") (pintype "passive"))
      (node (ref "InCon_2") (pin "2") (pinfunction "2_2") (pintype "passive"))
    )
    (net (code "33") (name "/Input_ch7-") (class "Default")
      (node (ref "C35") (pin "1") (pinfunction "1_1") (pintype "passive"))
      (node (ref "InCon_2") (pin "12") (pinfunction "12_12") (pintype "passive"))
    )
    (net (code "34") (name "/Input_ch8+") (class "Default")
      (node (ref "C36") (pin "1") (pinfunction "1_1") (pintype "passive"))
      (node (ref "InCon_2") (pin "1") (pinfunction "1_1") (pintype "passive"))
    )
    (net (code "35") (name "/Input_ch8-") (class "Default")
      (node (ref "C37") (pin "1") (pinfunction "1_1") (pintype "passive"))
      (node (ref "InCon_2") (pin "11") (pinfunction "11_11") (pintype "passive"))
    )
    (net (code "36") (name "/Output_ch1_N") (class "Default")
      (node (ref "OutCon1") (pin "A5") (pinfunction "5_A5") (pintype "passive"))
      (node (ref "U5") (pin "19") (pinfunction "D_-A_19") (pintype "output"))
    )
    (net (code "37") (name "/Output_ch1_P") (class "Default")
      (node (ref "OutCon1") (pin "A4") (pinfunction "4_A4") (pintype "passive"))
      (node (ref "U5") (pin "20") (pinfunction "D_+A_20") (pintype "output"))
    )
    (net (code "38") (name "/Output_ch2_N") (class "Default")
      (node (ref "OutCon1") (pin "A7") (pinfunction "7_A7") (pintype "passive"))
      (node (ref "U5") (pin "17") (pinfunction "D_-B_17") (pintype "output"))
    )
    (net (code "39") (name "/Output_ch2_P") (class "Default")
      (node (ref "OutCon1") (pin "A6") (pinfunction "6_A6") (pintype "passive"))
      (node (ref "U5") (pin "18") (pinfunction "D_+B_18") (pintype "output"))
    )
    (net (code "40") (name "/Output_ch3_N") (class "Default")
      (node (ref "OutCon1") (pin "A9") (pinfunction "9_A9") (pintype "passive"))
      (node (ref "U5") (pin "15") (pinfunction "D_-C_15") (pintype "output"))
    )
    (net (code "41") (name "/Output_ch3_P") (class "Default")
      (node (ref "OutCon1") (pin "A8") (pinfunction "8_A8") (pintype "passive"))
      (node (ref "U5") (pin "16") (pinfunction "D_+C_16") (pintype "output"))
    )
    (net (code "42") (name "/Output_ch4_N") (class "Default")
      (node (ref "OutCon1") (pin "A11") (pinfunction "11_A11") (pintype "passive"))
      (node (ref "U5") (pin "13") (pinfunction "D_-D_13") (pintype "output"))
    )
    (net (code "43") (name "/Output_ch4_P") (class "Default")
      (node (ref "OutCon1") (pin "A10") (pinfunction "10_A10") (pintype "passive"))
      (node (ref "U5") (pin "14") (pinfunction "D_+D_14") (pintype "output"))
    )
    (net (code "44") (name "/Output_ch5_N") (class "Default")
      (node (ref "OutCon1") (pin "A13") (pinfunction "13_A13") (pintype "passive"))
      (node (ref "U6") (pin "19") (pinfunction "D_-A_19") (pintype "output"))
    )
    (net (code "45") (name "/Output_ch5_P") (class "Default")
      (node (ref "OutCon1") (pin "A12") (pinfunction "12_A12") (pintype "passive"))
      (node (ref "U6") (pin "20") (pinfunction "D_+A_20") (pintype "output"))
    )
    (net (code "46") (name "/Output_ch6_N") (class "Default")
      (node (ref "OutCon1") (pin "A15") (pinfunction "15_A15") (pintype "passive"))
      (node (ref "U6") (pin "17") (pinfunction "D_-B_17") (pintype "output"))
    )
    (net (code "47") (name "/Output_ch6_P") (class "Default")
      (node (ref "OutCon1") (pin "A14") (pinfunction "14_A14") (pintype "passive"))
      (node (ref "U6") (pin "18") (pinfunction "D_+B_18") (pintype "output"))
    )
    (net (code "48") (name "/Output_ch7_N") (class "Default")
      (node (ref "OutCon1") (pin "A17") (pinfunction "17_A17") (pintype "passive"))
      (node (ref "U6") (pin "15") (pinfunction "D_-C_15") (pintype "output"))
    )
    (net (code "49") (name "/Output_ch7_P") (class "Default")
      (node (ref "OutCon1") (pin "A16") (pinfunction "16_A16") (pintype "passive"))
      (node (ref "U6") (pin "16") (pinfunction "D_+C_16") (pintype "output"))
    )
    (net (code "50") (name "/Output_ch8_N") (class "Default")
      (node (ref "OutCon1") (pin "A19") (pinfunction "19_A19") (pintype "passive"))
      (node (ref "U6") (pin "13") (pinfunction "D_-D_13") (pintype "output"))
    )
    (net (code "51") (name "/Output_ch8_P") (class "Default")
      (node (ref "OutCon1") (pin "A18") (pinfunction "18_A18") (pintype "passive"))
      (node (ref "U6") (pin "14") (pinfunction "D_+D_14") (pintype "output"))
    )
    (net (code "52") (name "/SCLK") (class "Default")
      (node (ref "OutCon1") (pin "A3") (pinfunction "3_A3") (pintype "passive"))
      (node (ref "U5") (pin "28") (pinfunction "SCLK/DTP_28") (pintype "input"))
      (node (ref "U6") (pin "28") (pinfunction "SCLK/DTP_28") (pintype "input"))
    )
    (net (code "53") (name "/SDIO{slash}ODM") (class "Default")
      (node (ref "OutCon1") (pin "A2") (pinfunction "2_A2") (pintype "passive"))
      (node (ref "U5") (pin "29") (pinfunction "SDIO/ODM_29") (pintype "bidirectional"))
      (node (ref "U6") (pin "29") (pinfunction "SDIO/ODM_29") (pintype "bidirectional"))
    )
    (net (code "54") (name "/Udiff_ch1_N") (class "Default")
      (node (ref "C18") (pin "1") (pinfunction "1_1") (pintype "passive"))
      (node (ref "R25") (pin "2") (pinfunction "2_2") (pintype "passive"))
      (node (ref "U5") (pin "34") (pinfunction "VIN_-A_34") (pintype "input"))
    )
    (net (code "55") (name "/Udiff_ch1_P") (class "Default")
      (node (ref "C19") (pin "2") (pinfunction "2_2") (pintype "passive"))
      (node (ref "R26") (pin "2") (pinfunction "2_2") (pintype "passive"))
      (node (ref "U5") (pin "33") (pinfunction "VIN_+A_33") (pintype "input"))
    )
    (net (code "56") (name "/Udiff_ch2_N") (class "Default")
      (node (ref "C20") (pin "1") (pinfunction "1_1") (pintype "passive"))
      (node (ref "R27") (pin "2") (pinfunction "2_2") (pintype "passive"))
      (node (ref "U5") (pin "37") (pinfunction "VIN_-B_37") (pintype "input"))
    )
    (net (code "57") (name "/Udiff_ch2_P") (class "Default")
      (node (ref "C21") (pin "2") (pinfunction "2_2") (pintype "passive"))
      (node (ref "R28") (pin "2") (pinfunction "2_2") (pintype "passive"))
      (node (ref "U5") (pin "38") (pinfunction "VIN_+B_38") (pintype "input"))
    )
    (net (code "58") (name "/Udiff_ch3_N") (class "Default")
      (node (ref "C22") (pin "1") (pinfunction "1_1") (pintype "passive"))
      (node (ref "R29") (pin "2") (pinfunction "2_2") (pintype "passive"))
      (node (ref "U5") (pin "48") (pinfunction "VIN_-C_48") (pintype "input"))
    )
    (net (code "59") (name "/Udiff_ch3_P") (class "Default")
      (node (ref "C23") (pin "2") (pinfunction "2_2") (pintype "passive"))
      (node (ref "R30") (pin "2") (pinfunction "2_2") (pintype "passive"))
      (node (ref "U5") (pin "47") (pinfunction "VIN_+C_47") (pintype "input"))
    )
    (net (code "60") (name "/Udiff_ch4_N") (class "Default")
      (node (ref "C24") (pin "1") (pinfunction "1_1") (pintype "passive"))
      (node (ref "R31") (pin "2") (pinfunction "2_2") (pintype "passive"))
      (node (ref "U5") (pin "3") (pinfunction "VIN_-D_3") (pintype "input"))
    )
    (net (code "61") (name "/Udiff_ch4_P") (class "Default")
      (node (ref "C25") (pin "2") (pinfunction "2_2") (pintype "passive"))
      (node (ref "R32") (pin "2") (pinfunction "2_2") (pintype "passive"))
      (node (ref "U5") (pin "4") (pinfunction "VIN_+D_4") (pintype "input"))
    )
    (net (code "62") (name "/Udiff_ch5_N") (class "Default")
      (node (ref "C42") (pin "1") (pinfunction "1_1") (pintype "passive"))
      (node (ref "R57") (pin "2") (pinfunction "2_2") (pintype "passive"))
      (node (ref "U6") (pin "34") (pinfunction "VIN_-A_34") (pintype "input"))
    )
    (net (code "63") (name "/Udiff_ch5_P") (class "Default")
      (node (ref "C43") (pin "2") (pinfunction "2_2") (pintype "passive"))
      (node (ref "R58") (pin "2") (pinfunction "2_2") (pintype "passive"))
      (node (ref "U6") (pin "33") (pinfunction "VIN_+A_33") (pintype "input"))
    )
    (net (code "64") (name "/Udiff_ch6_N") (class "Default")
      (node (ref "C44") (pin "1") (pinfunction "1_1") (pintype "passive"))
      (node (ref "R59") (pin "2") (pinfunction "2_2") (pintype "passive"))
      (node (ref "U6") (pin "37") (pinfunction "VIN_-B_37") (pintype "input"))
    )
    (net (code "65") (name "/Udiff_ch6_P") (class "Default")
      (node (ref "C45") (pin "2") (pinfunction "2_2") (pintype "passive"))
      (node (ref "R60") (pin "2") (pinfunction "2_2") (pintype "passive"))
      (node (ref "U6") (pin "38") (pinfunction "VIN_+B_38") (pintype "input"))
    )
    (net (code "66") (name "/Udiff_ch7_N") (class "Default")
      (node (ref "C46") (pin "1") (pinfunction "1_1") (pintype "passive"))
      (node (ref "R61") (pin "2") (pinfunction "2_2") (pintype "passive"))
      (node (ref "U6") (pin "48") (pinfunction "VIN_-C_48") (pintype "input"))
    )
    (net (code "67") (name "/Udiff_ch7_P") (class "Default")
      (node (ref "C47") (pin "2") (pinfunction "2_2") (pintype "passive"))
      (node (ref "R62") (pin "2") (pinfunction "2_2") (pintype "passive"))
      (node (ref "U6") (pin "47") (pinfunction "VIN_+C_47") (pintype "input"))
    )
    (net (code "68") (name "/Udiff_ch8_N") (class "Default")
      (node (ref "C48") (pin "1") (pinfunction "1_1") (pintype "passive"))
      (node (ref "R63") (pin "2") (pinfunction "2_2") (pintype "passive"))
      (node (ref "U6") (pin "3") (pinfunction "VIN_-D_3") (pintype "input"))
    )
    (net (code "69") (name "/Udiff_ch8_P") (class "Default")
      (node (ref "C49") (pin "2") (pinfunction "2_2") (pintype "passive"))
      (node (ref "R64") (pin "2") (pinfunction "2_2") (pintype "passive"))
      (node (ref "U6") (pin "4") (pinfunction "VIN_+D_4") (pintype "input"))
    )
    (net (code "70") (name "/VREF") (class "Default")
      (node (ref "C66") (pin "2") (pinfunction "2_2") (pintype "passive"))
      (node (ref "C67") (pin "2") (pinfunction "2_2") (pintype "passive"))
      (node (ref "C68") (pin "2") (pinfunction "2_2") (pintype "passive"))
      (node (ref "C69") (pin "2") (pinfunction "2_2") (pintype "passive"))
      (node (ref "U5") (pin "42") (pinfunction "VREF_42") (pintype "power_in"))
      (node (ref "U6") (pin "42") (pinfunction "VREF_42") (pintype "power_in"))
      (node (ref "Usup2") (pin "3") (pinfunction "+IN_3") (pintype "input"))
      (node (ref "Usup2") (pin "5") (pinfunction "+IN_5") (pintype "input"))
    )
    (net (code "71") (name "AGND") (class "Default")
      (node (ref "U5") (pin "0") (pinfunction "AGND_0") (pintype "power_in"))
      (node (ref "U6") (pin "0") (pinfunction "AGND_0") (pintype "power_in"))
    )
    (net (code "72") (name "GND") (class "Default")
      (node (ref "C1") (pin "1") (pinfunction "1_1") (pintype "passive"))
      (node (ref "C18") (pin "2") (pinfunction "2_2") (pintype "passive"))
      (node (ref "C19") (pin "1") (pinfunction "1_1") (pintype "passive"))
      (node (ref "C2") (pin "1") (pinfunction "1_1") (pintype "passive"))
      (node (ref "C20") (pin "2") (pinfunction "2_2") (pintype "passive"))
      (node (ref "C21") (pin "1") (pinfunction "1_1") (pintype "passive"))
      (node (ref "C22") (pin "2") (pinfunction "2_2") (pintype "passive"))
      (node (ref "C23") (pin "1") (pinfunction "1_1") (pintype "passive"))
      (node (ref "C24") (pin "2") (pinfunction "2_2") (pintype "passive"))
      (node (ref "C25") (pin "1") (pinfunction "1_1") (pintype "passive"))
      (node (ref "C26") (pin "1") (pinfunction "1_1") (pintype "passive"))
      (node (ref "C27") (pin "1") (pinfunction "1_1") (pintype "passive"))
      (node (ref "C28") (pin "1") (pinfunction "1_1") (pintype "passive"))
      (node (ref "C29") (pin "1") (pinfunction "1_1") (pintype "passive"))
      (node (ref "C3") (pin "1") (pinfunction "1_1") (pintype "passive"))
      (node (ref "C4") (pin "1") (pinfunction "1_1") (pintype "passive"))
      (node (ref "C42") (pin "2") (pinfunction "2_2") (pintype "passive"))
      (node (ref "C43") (pin "1") (pinfunction "1_1") (pintype "passive"))
      (node (ref "C44") (pin "2") (pinfunction "2_2") (pintype "passive"))
      (node (ref "C45") (pin "1") (pinfunction "1_1") (pintype "passive"))
      (node (ref "C46") (pin "2") (pinfunction "2_2") (pintype "passive"))
      (node (ref "C47") (pin "1") (pinfunction "1_1") (pintype "passive"))
      (node (ref "C48") (pin "2") (pinfunction "2_2") (pintype "passive"))
      (node (ref "C49") (pin "1") (pinfunction "1_1") (pintype "passive"))
      (node (ref "C5") (pin "1") (pinfunction "1_1") (pintype "passive"))
      (node (ref "C50") (pin "1") (pinfunction "1_1") (pintype "passive"))
      (node (ref "C51") (pin "1") (pinfunction "1_1") (pintype "passive"))
      (node (ref "C52") (pin "1") (pinfunction "1_1") (pintype "passive"))
      (node (ref "C53") (pin "1") (pinfunction "1_1") (pintype "passive"))
      (node (ref "C54") (pin "1") (pinfunction "1_1") (pintype "passive"))
      (node (ref "C55") (pin "1") (pinfunction "1_1") (pintype "passive"))
      (node (ref "C56") (pin "1") (pinfunction "1_1") (pintype "passive"))
      (node (ref "C57") (pin "1") (pinfunction "1_1") (pintype "passive"))
      (node (ref "C60") (pin "2") (pinfunction "2_2") (pintype "passive"))
      (node (ref "C62") (pin "1") (pinfunction "1_1") (pintype "passive"))
      (node (ref "C63") (pin "2") (pinfunction "2_2") (pintype "passive"))
      (node (ref "C65") (pin "1") (pinfunction "1_1") (pintype "passive"))
      (node (ref "C66") (pin "1") (pinfunction "1_1") (pintype "passive"))
      (node (ref "C67") (pin "1") (pinfunction "1_1") (pintype "passive"))
      (node (ref "C68") (pin "1") (pinfunction "1_1") (pintype "passive"))
      (node (ref "C69") (pin "1") (pinfunction "1_1") (pintype "passive"))
      (node (ref "C70") (pin "1") (pinfunction "1_1") (pintype "passive"))
      (node (ref "C71") (pin "1") (pinfunction "1_1") (pintype "passive"))
      (node (ref "C72") (pin "1") (pinfunction "1_1") (pintype "passive"))
      (node (ref "C73") (pin "1") (pinfunction "1_1") (pintype "passive"))
      (node (ref "C74") (pin "1") (pinfunction "1_1") (pintype "passive"))
      (node (ref "C75") (pin "1") (pinfunction "1_1") (pintype "passive"))
      (node (ref "C76") (pin "1") (pinfunction "1_1") (pintype "passive"))
      (node (ref "C77") (pin "1") (pinfunction "1_1") (pintype "passive"))
      (node (ref "C78") (pin "1") (pinfunction "1_1") (pintype "passive"))
      (node (ref "C79") (pin "1") (pinfunction "1_1") (pintype "passive"))
      (node (ref "C80") (pin "1") (pinfunction "1_1") (pintype "passive"))
      (node (ref "C81") (pin "1") (pinfunction "1_1") (pintype "passive"))
      (node (ref "C82") (pin "1") (pinfunction "1_1") (pintype "passive"))
      (node (ref "C83") (pin "1") (pinfunction "1_1") (pintype "passive"))
      (node (ref "Csup1") (pin "2") (pinfunction "2_2") (pintype "passive"))
      (node (ref "Csup2") (pin "+") (pinfunction "+_+") (pintype "passive"))
      (node (ref "Csup3") (pin "2") (pinfunction "2_2") (pintype "passive"))
      (node (ref "InCon_1") (pin "10") (pinfunction "10_10") (pintype "passive"))
      (node (ref "InCon_1") (pin "6") (pinfunction "6_6") (pintype "passive"))
      (node (ref "InCon_1") (pin "7") (pinfunction "7_7") (pintype "passive"))
      (node (ref "InCon_1") (pin "8") (pinfunction "8_8") (pintype "passive"))
      (node (ref "InCon_1") (pin "9") (pinfunction "9_9") (pintype "passive"))
      (node (ref "InCon_2") (pin "10") (pinfunction "10_10") (pintype "passive"))
      (node (ref "InCon_2") (pin "6") (pinfunction "6_6") (pintype "passive"))
      (node (ref "InCon_2") (pin "7") (pinfunction "7_7") (pintype "passive"))
      (node (ref "InCon_2") (pin "8") (pinfunction "8_8") (pintype "passive"))
      (node (ref "InCon_2") (pin "9") (pinfunction "9_9") (pintype "passive"))
      (node (ref "OutCon1") (pin "B10") (pinfunction "10_B10") (pintype "passive"))
      (node (ref "OutCon1") (pin "B12") (pinfunction "12_B12") (pintype "passive"))
      (node (ref "OutCon1") (pin "B14") (pinfunction "14_B14") (pintype "passive"))
      (node (ref "OutCon1") (pin "B4") (pinfunction "4_B4") (pintype "passive"))
      (node (ref "OutCon1") (pin "B6") (pinfunction "6_B6") (pintype "passive"))
      (node (ref "OutCon1") (pin "B8") (pinfunction "8_B8") (pintype "passive"))
      (node (ref "R65") (pin "2") (pinfunction "2_2") (pintype "passive"))
      (node (ref "R66") (pin "2") (pinfunction "2_2") (pintype "passive"))
      (node (ref "R70") (pin "2") (pinfunction "2_2") (pintype "passive"))
      (node (ref "R74") (pin "2") (pinfunction "2_2") (pintype "passive"))
      (node (ref "Rref1") (pin "2") (pinfunction "2_2") (pintype "passive"))
      (node (ref "U1") (pin "25") (pinfunction "Bottom_Pad_25") (pintype "passive"))
      (node (ref "U2") (pin "25") (pinfunction "Bottom_Pad_25") (pintype "passive"))
      (node (ref "U3") (pin "25") (pinfunction "Bottom_Pad_25") (pintype "passive"))
      (node (ref "U4") (pin "25") (pinfunction "Bottom_Pad_25") (pintype "passive"))
      (node (ref "U5") (pin "11") (pinfunction "DRGND_11") (pintype "power_in"))
      (node (ref "U5") (pin "26") (pinfunction "DRGND_26") (pintype "power_in"))
      (node (ref "U5") (pin "41") (pinfunction "SENSE_41") (pintype "passive"))
      (node (ref "U6") (pin "11") (pinfunction "DRGND_11") (pintype "power_in"))
      (node (ref "U6") (pin "26") (pinfunction "DRGND_26") (pintype "power_in"))
      (node (ref "U6") (pin "41") (pinfunction "SENSE_41") (pintype "passive"))
      (node (ref "Usup2") (pin "4") (pinfunction "E-_4") (pintype "input"))
    )
    (net (code "73") (name "Net-(C6-Pad2)") (class "Default")
      (node (ref "C6") (pin "2") (pinfunction "2_2") (pintype "passive"))
      (node (ref "R1") (pin "2") (pinfunction "2_2") (pintype "passive"))
      (node (ref "R9") (pin "2") (pinfunction "2_2") (pintype "passive"))
    )
    (net (code "74") (name "Net-(C7-Pad2)") (class "Default")
      (node (ref "C7") (pin "2") (pinfunction "2_2") (pintype "passive"))
      (node (ref "R10") (pin "2") (pinfunction "2_2") (pintype "passive"))
      (node (ref "R2") (pin "1") (pinfunction "1_1") (pintype "passive"))
    )
    (net (code "75") (name "Net-(C8-Pad2)") (class "Default")
      (node (ref "C8") (pin "2") (pinfunction "2_2") (pintype "passive"))
      (node (ref "R11") (pin "2") (pinfunction "2_2") (pintype "passive"))
      (node (ref "R3") (pin "2") (pinfunction "2_2") (pintype "passive"))
    )
    (net (code "76") (name "Net-(C9-Pad2)") (class "Default")
      (node (ref "C9") (pin "2") (pinfunction "2_2") (pintype "passive"))
      (node (ref "R12") (pin "2") (pinfunction "2_2") (pintype "passive"))
      (node (ref "R4") (pin "1") (pinfunction "1_1") (pintype "passive"))
    )
    (net (code "77") (name "Net-(C10-Pad2)") (class "Default")
      (node (ref "C10") (pin "2") (pinfunction "2_2") (pintype "passive"))
      (node (ref "R13") (pin "2") (pinfunction "2_2") (pintype "passive"))
      (node (ref "R5") (pin "2") (pinfunction "2_2") (pintype "passive"))
    )
    (net (code "78") (name "Net-(C11-Pad2)") (class "Default")
      (node (ref "C11") (pin "2") (pinfunction "2_2") (pintype "passive"))
      (node (ref "R14") (pin "2") (pinfunction "2_2") (pintype "passive"))
      (node (ref "R6") (pin "1") (pinfunction "1_1") (pintype "passive"))
    )
    (net (code "79") (name "Net-(C12-Pad2)") (class "Default")
      (node (ref "C12") (pin "2") (pinfunction "2_2") (pintype "passive"))
      (node (ref "R15") (pin "2") (pinfunction "2_2") (pintype "passive"))
      (node (ref "R7") (pin "2") (pinfunction "2_2") (pintype "passive"))
    )
    (net (code "80") (name "Net-(C13-Pad2)") (class "Default")
      (node (ref "C13") (pin "2") (pinfunction "2_2") (pintype "passive"))
      (node (ref "R16") (pin "2") (pinfunction "2_2") (pintype "passive"))
      (node (ref "R8") (pin "1") (pinfunction "1_1") (pintype "passive"))
    )
    (net (code "81") (name "Net-(C30-Pad2)") (class "Default")
      (node (ref "C30") (pin "2") (pinfunction "2_2") (pintype "passive"))
      (node (ref "R33") (pin "2") (pinfunction "2_2") (pintype "passive"))
      (node (ref "R41") (pin "2") (pinfunction "2_2") (pintype "passive"))
    )
    (net (code "82") (name "Net-(C31-Pad2)") (class "Default")
      (node (ref "C31") (pin "2") (pinfunction "2_2") (pintype "passive"))
      (node (ref "R34") (pin "1") (pinfunction "1_1") (pintype "passive"))
      (node (ref "R42") (pin "2") (pinfunction "2_2") (pintype "passive"))
    )
    (net (code "83") (name "Net-(C32-Pad2)") (class "Default")
      (node (ref "C32") (pin "2") (pinfunction "2_2") (pintype "passive"))
      (node (ref "R35") (pin "2") (pinfunction "2_2") (pintype "passive"))
      (node (ref "R43") (pin "2") (pinfunction "2_2") (pintype "passive"))
    )
    (net (code "84") (name "Net-(C33-Pad2)") (class "Default")
      (node (ref "C33") (pin "2") (pinfunction "2_2") (pintype "passive"))
      (node (ref "R36") (pin "1") (pinfunction "1_1") (pintype "passive"))
      (node (ref "R44") (pin "2") (pinfunction "2_2") (pintype "passive"))
    )
    (net (code "85") (name "Net-(C34-Pad2)") (class "Default")
      (node (ref "C34") (pin "2") (pinfunction "2_2") (pintype "passive"))
      (node (ref "R37") (pin "2") (pinfunction "2_2") (pintype "passive"))
      (node (ref "R45") (pin "2") (pinfunction "2_2") (pintype "passive"))
    )
    (net (code "86") (name "Net-(C35-Pad2)") (class "Default")
      (node (ref "C35") (pin "2") (pinfunction "2_2") (pintype "passive"))
      (node (ref "R38") (pin "1") (pinfunction "1_1") (pintype "passive"))
      (node (ref "R46") (pin "2") (pinfunction "2_2") (pintype "passive"))
    )
    (net (code "87") (name "Net-(C36-Pad2)") (class "Default")
      (node (ref "C36") (pin "2") (pinfunction "2_2") (pintype "passive"))
      (node (ref "R39") (pin "2") (pinfunction "2_2") (pintype "passive"))
      (node (ref "R47") (pin "2") (pinfunction "2_2") (pintype "passive"))
    )
    (net (code "88") (name "Net-(C37-Pad2)") (class "Default")
      (node (ref "C37") (pin "2") (pinfunction "2_2") (pintype "passive"))
      (node (ref "R40") (pin "1") (pinfunction "1_1") (pintype "passive"))
      (node (ref "R48") (pin "2") (pinfunction "2_2") (pintype "passive"))
    )
    (net (code "89") (name "Net-(U1A-FB1+)") (class "Default")
      (node (ref "R18") (pin "1") (pinfunction "1_1") (pintype "passive"))
      (node (ref "U1") (pin "2") (pinfunction "FB1+_2") (pintype "output"))
    )
    (net (code "90") (name "Net-(U1A-FB1-)") (class "Default")
      (node (ref "R17") (pin "2") (pinfunction "2_2") (pintype "passive"))
      (node (ref "U1") (pin "23") (pinfunction "FB1-_23") (pintype "output"))
    )
    (net (code "91") (name "Net-(U1A-In+)") (class "Default")
      (node (ref "R17") (pin "1") (pinfunction "1_1") (pintype "passive"))
      (node (ref "R9") (pin "1") (pinfunction "1_1") (pintype "passive"))
      (node (ref "U1") (pin "24") (pinfunction "In+_24") (pintype "input"))
    )
    (net (code "92") (name "Net-(U1A-In-)") (class "Default")
      (node (ref "R10") (pin "1") (pinfunction "1_1") (pintype "passive"))
      (node (ref "R18") (pin "2") (pinfunction "2_2") (pintype "passive"))
      (node (ref "U1") (pin "1") (pinfunction "In-_1") (pintype "input"))
    )
    (net (code "93") (name "Net-(U1A-Out+)") (class "Default")
      (node (ref "R26") (pin "1") (pinfunction "1_1") (pintype "passive"))
      (node (ref "U1") (pin "18") (pinfunction "Out+_18") (pintype "output"))
    )
    (net (code "94") (name "Net-(U1A-Out-)") (class "Default")
      (node (ref "R25") (pin "1") (pinfunction "1_1") (pintype "passive"))
      (node (ref "U1") (pin "19") (pinfunction "Out-_19") (pintype "output"))
    )
    (net (code "95") (name "Net-(U1B-FB2+)") (class "Default")
      (node (ref "R20") (pin "1") (pinfunction "1_1") (pintype "passive"))
      (node (ref "U1") (pin "8") (pinfunction "FB2+_8") (pintype "output"))
    )
    (net (code "96") (name "Net-(U1B-FB2-)") (class "Default")
      (node (ref "R19") (pin "2") (pinfunction "2_2") (pintype "passive"))
      (node (ref "U1") (pin "5") (pinfunction "FB2-_5") (pintype "output"))
    )
    (net (code "97") (name "Net-(U1B-In+)") (class "Default")
      (node (ref "R11") (pin "1") (pinfunction "1_1") (pintype "passive"))
      (node (ref "R19") (pin "1") (pinfunction "1_1") (pintype "passive"))
      (node (ref "U1") (pin "6") (pinfunction "In+_6") (pintype "input"))
    )
    (net (code "98") (name "Net-(U1B-In-)") (class "Default")
      (node (ref "R12") (pin "1") (pinfunction "1_1") (pintype "passive"))
      (node (ref "R20") (pin "2") (pinfunction "2_2") (pintype "passive"))
      (node (ref "U1") (pin "7") (pinfunction "In-_7") (pintype "input"))
    )
    (net (code "99") (name "Net-(U1B-Out+)") (class "Default")
      (node (ref "R28") (pin "1") (pinfunction "1_1") (pintype "passive"))
      (node (ref "U1") (pin "12") (pinfunction "Out+_12") (pintype "output"))
    )
    (net (code "100") (name "Net-(U1B-Out-)") (class "Default")
      (node (ref "R27") (pin "1") (pinfunction "1_1") (pintype "passive"))
      (node (ref "U1") (pin "13") (pinfunction "Out-_13") (pintype "output"))
    )
    (net (code "101") (name "Net-(U2A-FB1+)") (class "Default")
      (node (ref "R22") (pin "1") (pinfunction "1_1") (pintype "passive"))
      (node (ref "U2") (pin "2") (pinfunction "FB1+_2") (pintype "output"))
    )
    (net (code "102") (name "Net-(U2A-FB1-)") (class "Default")
      (node (ref "R21") (pin "2") (pinfunction "2_2") (pintype "passive"))
      (node (ref "U2") (pin "23") (pinfunction "FB1-_23") (pintype "output"))
    )
    (net (code "103") (name "Net-(U2A-In+)") (class "Default")
      (node (ref "R13") (pin "1") (pinfunction "1_1") (pintype "passive"))
      (node (ref "R21") (pin "1") (pinfunction "1_1") (pintype "passive"))
      (node (ref "U2") (pin "24") (pinfunction "In+_24") (pintype "input"))
    )
    (net (code "104") (name "Net-(U2A-In-)") (class "Default")
      (node (ref "R14") (pin "1") (pinfunction "1_1") (pintype "passive"))
      (node (ref "R22") (pin "2") (pinfunction "2_2") (pintype "passive"))
      (node (ref "U2") (pin "1") (pinfunction "In-_1") (pintype "input"))
    )
    (net (code "105") (name "Net-(U2A-Out+)") (class "Default")
      (node (ref "R30") (pin "1") (pinfunction "1_1") (pintype "passive"))
      (node (ref "U2") (pin "18") (pinfunction "Out+_18") (pintype "output"))
    )
    (net (code "106") (name "Net-(U2A-Out-)") (class "Default")
      (node (ref "R29") (pin "1") (pinfunction "1_1") (pintype "passive"))
      (node (ref "U2") (pin "19") (pinfunction "Out-_19") (pintype "output"))
    )
    (net (code "107") (name "Net-(U2B-FB2+)") (class "Default")
      (node (ref "R24") (pin "1") (pinfunction "1_1") (pintype "passive"))
      (node (ref "U2") (pin "8") (pinfunction "FB2+_8") (pintype "output"))
    )
    (net (code "108") (name "Net-(U2B-FB2-)") (class "Default")
      (node (ref "R23") (pin "2") (pinfunction "2_2") (pintype "passive"))
      (node (ref "U2") (pin "5") (pinfunction "FB2-_5") (pintype "output"))
    )
    (net (code "109") (name "Net-(U2B-In+)") (class "Default")
      (node (ref "R15") (pin "1") (pinfunction "1_1") (pintype "passive"))
      (node (ref "R23") (pin "1") (pinfunction "1_1") (pintype "passive"))
      (node (ref "U2") (pin "6") (pinfunction "In+_6") (pintype "input"))
    )
    (net (code "110") (name "Net-(U2B-In-)") (class "Default")
      (node (ref "R16") (pin "1") (pinfunction "1_1") (pintype "passive"))
      (node (ref "R24") (pin "2") (pinfunction "2_2") (pintype "passive"))
      (node (ref "U2") (pin "7") (pinfunction "In-_7") (pintype "input"))
    )
    (net (code "111") (name "Net-(U2B-Out+)") (class "Default")
      (node (ref "R32") (pin "1") (pinfunction "1_1") (pintype "passive"))
      (node (ref "U2") (pin "12") (pinfunction "Out+_12") (pintype "output"))
    )
    (net (code "112") (name "Net-(U2B-Out-)") (class "Default")
      (node (ref "R31") (pin "1") (pinfunction "1_1") (pintype "passive"))
      (node (ref "U2") (pin "13") (pinfunction "Out-_13") (pintype "output"))
    )
    (net (code "113") (name "Net-(U3A-FB1+)") (class "Default")
      (node (ref "R50") (pin "1") (pinfunction "1_1") (pintype "passive"))
      (node (ref "U3") (pin "2") (pinfunction "FB1+_2") (pintype "output"))
    )
    (net (code "114") (name "Net-(U3A-FB1-)") (class "Default")
      (node (ref "R49") (pin "2") (pinfunction "2_2") (pintype "passive"))
      (node (ref "U3") (pin "23") (pinfunction "FB1-_23") (pintype "output"))
    )
    (net (code "115") (name "Net-(U3A-In+)") (class "Default")
      (node (ref "R41") (pin "1") (pinfunction "1_1") (pintype "passive"))
      (node (ref "R49") (pin "1") (pinfunction "1_1") (pintype "passive"))
      (node (ref "U3") (pin "24") (pinfunction "In+_24") (pintype "input"))
    )
    (net (code "116") (name "Net-(U3A-In-)") (class "Default")
      (node (ref "R42") (pin "1") (pinfunction "1_1") (pintype "passive"))
      (node (ref "R50") (pin "2") (pinfunction "2_2") (pintype "passive"))
      (node (ref "U3") (pin "1") (pinfunction "In-_1") (pintype "input"))
    )
    (net (code "117") (name "Net-(U3A-Out+)") (class "Default")
      (node (ref "R58") (pin "1") (pinfunction "1_1") (pintype "passive"))
      (node (ref "U3") (pin "18") (pinfunction "Out+_18") (pintype "output"))
    )
    (net (code "118") (name "Net-(U3A-Out-)") (class "Default")
      (node (ref "R57") (pin "1") (pinfunction "1_1") (pintype "passive"))
      (node (ref "U3") (pin "19") (pinfunction "Out-_19") (pintype "output"))
    )
    (net (code "119") (name "Net-(U3B-FB2+)") (class "Default")
      (node (ref "R52") (pin "1") (pinfunction "1_1") (pintype "passive"))
      (node (ref "U3") (pin "8") (pinfunction "FB2+_8") (pintype "output"))
    )
    (net (code "120") (name "Net-(U3B-FB2-)") (class "Default")
      (node (ref "R51") (pin "2") (pinfunction "2_2") (pintype "passive"))
      (node (ref "U3") (pin "5") (pinfunction "FB2-_5") (pintype "output"))
    )
    (net (code "121") (name "Net-(U3B-In+)") (class "Default")
      (node (ref "R43") (pin "1") (pinfunction "1_1") (pintype "passive"))
      (node (ref "R51") (pin "1") (pinfunction "1_1") (pintype "passive"))
      (node (ref "U3") (pin "6") (pinfunction "In+_6") (pintype "input"))
    )
    (net (code "122") (name "Net-(U3B-In-)") (class "Default")
      (node (ref "R44") (pin "1") (pinfunction "1_1") (pintype "passive"))
      (node (ref "R52") (pin "2") (pinfunction "2_2") (pintype "passive"))
      (node (ref "U3") (pin "7") (pinfunction "In-_7") (pintype "input"))
    )
    (net (code "123") (name "Net-(U3B-Out+)") (class "Default")
      (node (ref "R60") (pin "1") (pinfunction "1_1") (pintype "passive"))
      (node (ref "U3") (pin "12") (pinfunction "Out+_12") (pintype "output"))
    )
    (net (code "124") (name "Net-(U3B-Out-)") (class "Default")
      (node (ref "R59") (pin "1") (pinfunction "1_1") (pintype "passive"))
      (node (ref "U3") (pin "13") (pinfunction "Out-_13") (pintype "output"))
    )
    (net (code "125") (name "Net-(U4A-FB1+)") (class "Default")
      (node (ref "R54") (pin "1") (pinfunction "1_1") (pintype "passive"))
      (node (ref "U4") (pin "2") (pinfunction "FB1+_2") (pintype "output"))
    )
    (net (code "126") (name "Net-(U4A-FB1-)") (class "Default")
      (node (ref "R53") (pin "2") (pinfunction "2_2") (pintype "passive"))
      (node (ref "U4") (pin "23") (pinfunction "FB1-_23") (pintype "output"))
    )
    (net (code "127") (name "Net-(U4A-In+)") (class "Default")
      (node (ref "R45") (pin "1") (pinfunction "1_1") (pintype "passive"))
      (node (ref "R53") (pin "1") (pinfunction "1_1") (pintype "passive"))
      (node (ref "U4") (pin "24") (pinfunction "In+_24") (pintype "input"))
    )
    (net (code "128") (name "Net-(U4A-In-)") (class "Default")
      (node (ref "R46") (pin "1") (pinfunction "1_1") (pintype "passive"))
      (node (ref "R54") (pin "2") (pinfunction "2_2") (pintype "passive"))
      (node (ref "U4") (pin "1") (pinfunction "In-_1") (pintype "input"))
    )
    (net (code "129") (name "Net-(U4A-Out+)") (class "Default")
      (node (ref "R62") (pin "1") (pinfunction "1_1") (pintype "passive"))
      (node (ref "U4") (pin "18") (pinfunction "Out+_18") (pintype "output"))
    )
    (net (code "130") (name "Net-(U4A-Out-)") (class "Default")
      (node (ref "R61") (pin "1") (pinfunction "1_1") (pintype "passive"))
      (node (ref "U4") (pin "19") (pinfunction "Out-_19") (pintype "output"))
    )
    (net (code "131") (name "Net-(U4B-FB2+)") (class "Default")
      (node (ref "R56") (pin "1") (pinfunction "1_1") (pintype "passive"))
      (node (ref "U4") (pin "8") (pinfunction "FB2+_8") (pintype "output"))
    )
    (net (code "132") (name "Net-(U4B-FB2-)") (class "Default")
      (node (ref "R55") (pin "2") (pinfunction "2_2") (pintype "passive"))
      (node (ref "U4") (pin "5") (pinfunction "FB2-_5") (pintype "output"))
    )
    (net (code "133") (name "Net-(U4B-In+)") (class "Default")
      (node (ref "R47") (pin "1") (pinfunction "1_1") (pintype "passive"))
      (node (ref "R55") (pin "1") (pinfunction "1_1") (pintype "passive"))
      (node (ref "U4") (pin "6") (pinfunction "In+_6") (pintype "input"))
    )
    (net (code "134") (name "Net-(U4B-In-)") (class "Default")
      (node (ref "R48") (pin "1") (pinfunction "1_1") (pintype "passive"))
      (node (ref "R56") (pin "2") (pinfunction "2_2") (pintype "passive"))
      (node (ref "U4") (pin "7") (pinfunction "In-_7") (pintype "input"))
    )
    (net (code "135") (name "Net-(U4B-Out+)") (class "Default")
      (node (ref "R64") (pin "1") (pinfunction "1_1") (pintype "passive"))
      (node (ref "U4") (pin "12") (pinfunction "Out+_12") (pintype "output"))
    )
    (net (code "136") (name "Net-(U4B-Out-)") (class "Default")
      (node (ref "R63") (pin "1") (pinfunction "1_1") (pintype "passive"))
      (node (ref "U4") (pin "13") (pinfunction "Out-_13") (pintype "output"))
    )
    (net (code "137") (name "Net-(U5-RBIAS)") (class "Default")
      (node (ref "R65") (pin "1") (pinfunction "1_1") (pintype "passive"))
      (node (ref "U5") (pin "40") (pinfunction "RBIAS_40") (pintype "passive"))
    )
    (net (code "138") (name "Net-(U5-REFB)") (class "Default")
      (node (ref "C58") (pin "-") (pinfunction "-_-") (pintype "passive"))
      (node (ref "C60") (pin "1") (pinfunction "1_1") (pintype "passive"))
      (node (ref "C61") (pin "2") (pinfunction "2_2") (pintype "passive"))
      (node (ref "U5") (pin "43") (pinfunction "REFB_43") (pintype "passive"))
    )
    (net (code "139") (name "Net-(U5-REFT)") (class "Default")
      (node (ref "C58") (pin "+") (pinfunction "+_+") (pintype "passive"))
      (node (ref "C61") (pin "1") (pinfunction "1_1") (pintype "passive"))
      (node (ref "C62") (pin "2") (pinfunction "2_2") (pintype "passive"))
      (node (ref "U5") (pin "44") (pinfunction "REFT_44") (pintype "passive"))
    )
    (net (code "140") (name "Net-(U6-RBIAS)") (class "Default")
      (node (ref "R66") (pin "1") (pinfunction "1_1") (pintype "passive"))
      (node (ref "U6") (pin "40") (pinfunction "RBIAS_40") (pintype "passive"))
    )
    (net (code "141") (name "Net-(U6-REFB)") (class "Default")
      (node (ref "C59") (pin "-") (pinfunction "-_-") (pintype "passive"))
      (node (ref "C63") (pin "1") (pinfunction "1_1") (pintype "passive"))
      (node (ref "C64") (pin "2") (pinfunction "2_2") (pintype "passive"))
      (node (ref "U6") (pin "43") (pinfunction "REFB_43") (pintype "passive"))
    )
    (net (code "142") (name "Net-(U6-REFT)") (class "Default")
      (node (ref "C59") (pin "+") (pinfunction "+_+") (pintype "passive"))
      (node (ref "C64") (pin "1") (pinfunction "1_1") (pintype "passive"))
      (node (ref "C65") (pin "2") (pinfunction "2_2") (pintype "passive"))
      (node (ref "U6") (pin "44") (pinfunction "REFT_44") (pintype "passive"))
    )
    (net (code "143") (name "Net-(Usup1-Adj)") (class "Default")
      (node (ref "Rref1") (pin "1") (pinfunction "1_1") (pintype "passive"))
      (node (ref "Rref2") (pin "2") (pinfunction "2_2") (pintype "passive"))
      (node (ref "Usup1") (pin "1") (pinfunction "Adj_1") (pintype "passive"))
    )
    (net (code "144") (name "Net-(Usup2A--IN)") (class "Default")
      (node (ref "C84") (pin "2") (pinfunction "2_2") (pintype "passive"))
      (node (ref "R68") (pin "1") (pinfunction "1_1") (pintype "passive"))
      (node (ref "Usup2") (pin "2") (pinfunction "-IN_2") (pintype "input"))
    )
    (net (code "145") (name "Net-(Usup2A-OUT)") (class "Default")
      (node (ref "C84") (pin "1") (pinfunction "1_1") (pintype "passive"))
      (node (ref "R67") (pin "1") (pinfunction "1_1") (pintype "passive"))
      (node (ref "Usup2") (pin "1") (pinfunction "OUT_1") (pintype "output"))
    )
    (net (code "146") (name "Net-(Usup2B--IN)") (class "Default")
      (node (ref "C85") (pin "2") (pinfunction "2_2") (pintype "passive"))
      (node (ref "R72") (pin "1") (pinfunction "1_1") (pintype "passive"))
      (node (ref "Usup2") (pin "6") (pinfunction "-IN_6") (pintype "input"))
    )
    (net (code "147") (name "Net-(Usup2B-OUT)") (class "Default")
      (node (ref "C85") (pin "1") (pinfunction "1_1") (pintype "passive"))
      (node (ref "R71") (pin "1") (pinfunction "1_1") (pintype "passive"))
      (node (ref "Usup2") (pin "7") (pinfunction "OUT_7") (pintype "output"))
    )
    (net (code "148") (name "VOffset+") (class "Default")
      (node (ref "C14") (pin "2") (pinfunction "2_2") (pintype "passive"))
      (node (ref "C15") (pin "2") (pinfunction "2_2") (pintype "passive"))
      (node (ref "C16") (pin "2") (pinfunction "2_2") (pintype "passive"))
      (node (ref "C17") (pin "2") (pinfunction "2_2") (pintype "passive"))
      (node (ref "C38") (pin "2") (pinfunction "2_2") (pintype "passive"))
      (node (ref "C39") (pin "2") (pinfunction "2_2") (pintype "passive"))
      (node (ref "C40") (pin "2") (pinfunction "2_2") (pintype "passive"))
      (node (ref "C41") (pin "2") (pinfunction "2_2") (pintype "passive"))
      (node (ref "R1") (pin "1") (pinfunction "1_1") (pintype "passive"))
      (node (ref "R3") (pin "1") (pinfunction "1_1") (pintype "passive"))
      (node (ref "R33") (pin "1") (pinfunction "1_1") (pintype "passive"))
      (node (ref "R35") (pin "1") (pinfunction "1_1") (pintype "passive"))
      (node (ref "R37") (pin "1") (pinfunction "1_1") (pintype "passive"))
      (node (ref "R39") (pin "1") (pinfunction "1_1") (pintype "passive"))
      (node (ref "R5") (pin "1") (pinfunction "1_1") (pintype "passive"))
      (node (ref "R7") (pin "1") (pinfunction "1_1") (pintype "passive"))
      (node (ref "R70") (pin "1") (pinfunction "1_1") (pintype "passive"))
      (node (ref "R74") (pin "1") (pinfunction "1_1") (pintype "passive"))
    )
    (net (code "149") (name "Vcm") (class "Default")
      (node (ref "C1") (pin "2") (pinfunction "2_2") (pintype "passive"))
      (node (ref "C14") (pin "1") (pinfunction "1_1") (pintype "passive"))
      (node (ref "C15") (pin "1") (pinfunction "1_1") (pintype "passive"))
      (node (ref "C16") (pin "1") (pinfunction "1_1") (pintype "passive"))
      (node (ref "C17") (pin "1") (pinfunction "1_1") (pintype "passive"))
      (node (ref "C2") (pin "2") (pinfunction "2_2") (pintype "passive"))
      (node (ref "C26") (pin "2") (pinfunction "2_2") (pintype "passive"))
      (node (ref "C27") (pin "2") (pinfunction "2_2") (pintype "passive"))
      (node (ref "C28") (pin "2") (pinfunction "2_2") (pintype "passive"))
      (node (ref "C29") (pin "2") (pinfunction "2_2") (pintype "passive"))
      (node (ref "C3") (pin "2") (pinfunction "2_2") (pintype "passive"))
      (node (ref "C38") (pin "1") (pinfunction "1_1") (pintype "passive"))
      (node (ref "C39") (pin "1") (pinfunction "1_1") (pintype "passive"))
      (node (ref "C4") (pin "2") (pinfunction "2_2") (pintype "passive"))
      (node (ref "C40") (pin "1") (pinfunction "1_1") (pintype "passive"))
      (node (ref "C41") (pin "1") (pinfunction "1_1") (pintype "passive"))
      (node (ref "C5") (pin "2") (pinfunction "2_2") (pintype "passive"))
      (node (ref "R2") (pin "2") (pinfunction "2_2") (pintype "passive"))
      (node (ref "R34") (pin "2") (pinfunction "2_2") (pintype "passive"))
      (node (ref "R36") (pin "2") (pinfunction "2_2") (pintype "passive"))
      (node (ref "R38") (pin "2") (pinfunction "2_2") (pintype "passive"))
      (node (ref "R4") (pin "2") (pinfunction "2_2") (pintype "passive"))
      (node (ref "R40") (pin "2") (pinfunction "2_2") (pintype "passive"))
      (node (ref "R6") (pin "2") (pinfunction "2_2") (pintype "passive"))
      (node (ref "R67") (pin "2") (pinfunction "2_2") (pintype "passive"))
      (node (ref "R68") (pin "2") (pinfunction "2_2") (pintype "passive"))
      (node (ref "R71") (pin "2") (pinfunction "2_2") (pintype "passive"))
      (node (ref "R72") (pin "2") (pinfunction "2_2") (pintype "passive"))
      (node (ref "R8") (pin "2") (pinfunction "2_2") (pintype "passive"))
      (node (ref "U1") (pin "11") (pinfunction "Vocm_11") (pintype "input"))
      (node (ref "U1") (pin "17") (pinfunction "Vocm_17") (pintype "input"))
      (node (ref "U2") (pin "11") (pinfunction "Vocm_11") (pintype "input"))
      (node (ref "U2") (pin "17") (pinfunction "Vocm_17") (pintype "input"))
      (node (ref "U3") (pin "11") (pinfunction "Vocm_11") (pintype "input"))
      (node (ref "U3") (pin "17") (pinfunction "Vocm_17") (pintype "input"))
      (node (ref "U4") (pin "11") (pinfunction "Vocm_11") (pintype "input"))
      (node (ref "U4") (pin "17") (pinfunction "Vocm_17") (pintype "input"))
    )
    (net (code "150") (name "unconnected-(InCon_1-Pad15)") (class "Default")
      (node (ref "InCon_1") (pin "15") (pinfunction "15_15") (pintype "passive"))
    )
    (net (code "151") (name "unconnected-(InCon_2-Pad15)") (class "Default")
      (node (ref "InCon_2") (pin "15") (pinfunction "15_15") (pintype "passive"))
    )
    (net (code "152") (name "unconnected-(OutCon1-2-PadB2)") (class "Default")
      (node (ref "OutCon1") (pin "B2") (pinfunction "2_B2") (pintype "passive"))
    )
    (net (code "153") (name "unconnected-(OutCon1-5-PadB5)") (class "Default")
      (node (ref "OutCon1") (pin "B5") (pinfunction "5_B5") (pintype "passive"))
    )
    (net (code "154") (name "unconnected-(OutCon1-7-PadB7)") (class "Default")
      (node (ref "OutCon1") (pin "B7") (pinfunction "7_B7") (pintype "passive"))
    )
    (net (code "155") (name "unconnected-(OutCon1-9-PadB9)") (class "Default")
      (node (ref "OutCon1") (pin "B9") (pinfunction "9_B9") (pintype "passive"))
    )
    (net (code "156") (name "unconnected-(OutCon1-11-PadB11)") (class "Default")
      (node (ref "OutCon1") (pin "B11") (pinfunction "11_B11") (pintype "passive"))
    )
    (net (code "157") (name "unconnected-(OutCon1-13-PadB13)") (class "Default")
      (node (ref "OutCon1") (pin "B13") (pinfunction "13_B13") (pintype "passive"))
    )
    (net (code "158") (name "unconnected-(OutCon1-PadA25)") (class "Default")
      (node (ref "OutCon1") (pin "A25") (pinfunction "A25_A25") (pintype "passive"))
    )
    (net (code "159") (name "unconnected-(OutCon1-PadA26)") (class "Default")
      (node (ref "OutCon1") (pin "A26") (pinfunction "A26_A26") (pintype "passive"))
    )
    (net (code "160") (name "unconnected-(OutCon1-PadB24)") (class "Default")
      (node (ref "OutCon1") (pin "B24") (pinfunction "B24_B24") (pintype "passive"))
    )
    (net (code "161") (name "unconnected-(OutCon1-PadB26)") (class "Default")
      (node (ref "OutCon1") (pin "B26") (pinfunction "B26_B26") (pintype "passive"))
    )
    (net (code "162") (name "unconnected-(R69-Pad1)") (class "Default")
      (node (ref "R69") (pin "1") (pinfunction "1_1") (pintype "passive"))
    )
    (net (code "163") (name "unconnected-(R69-Pad2)") (class "Default")
      (node (ref "R69") (pin "2") (pinfunction "2_2") (pintype "passive"))
    )
    (net (code "164") (name "unconnected-(R73-Pad1)") (class "Default")
      (node (ref "R73") (pin "1") (pinfunction "1_1") (pintype "passive"))
    )
    (net (code "165") (name "unconnected-(R73-Pad2)") (class "Default")
      (node (ref "R73") (pin "2") (pinfunction "2_2") (pintype "passive"))
    )
    (net (code "166") (name "unconnected-(U1C-PD1-Pad20)") (class "Default")
      (node (ref "U1") (pin "20") (pinfunction "PD1_20") (pintype "passive"))
    )
    (net (code "167") (name "unconnected-(U1C-PD2-Pad14)") (class "Default")
      (node (ref "U1") (pin "14") (pinfunction "PD2_14") (pintype "passive"))
    )
    (net (code "168") (name "unconnected-(U2C-PD1-Pad20)") (class "Default")
      (node (ref "U2") (pin "20") (pinfunction "PD1_20") (pintype "passive"))
    )
    (net (code "169") (name "unconnected-(U2C-PD2-Pad14)") (class "Default")
      (node (ref "U2") (pin "14") (pinfunction "PD2_14") (pintype "passive"))
    )
    (net (code "170") (name "unconnected-(U3C-PD1-Pad20)") (class "Default")
      (node (ref "U3") (pin "20") (pinfunction "PD1_20") (pintype "passive"))
    )
    (net (code "171") (name "unconnected-(U3C-PD2-Pad14)") (class "Default")
      (node (ref "U3") (pin "14") (pinfunction "PD2_14") (pintype "passive"))
    )
    (net (code "172") (name "unconnected-(U4C-PD1-Pad20)") (class "Default")
      (node (ref "U4") (pin "20") (pinfunction "PD1_20") (pintype "passive"))
    )
    (net (code "173") (name "unconnected-(U4C-PD2-Pad14)") (class "Default")
      (node (ref "U4") (pin "14") (pinfunction "PD2_14") (pintype "passive"))
    )
    (net (code "174") (name "unconnected-(U5-PWDN-Pad31)") (class "Default")
      (node (ref "U5") (pin "31") (pinfunction "PWDN_31") (pintype "passive"))
    )
    (net (code "175") (name "unconnected-(U6-PWDN-Pad31)") (class "Default")
      (node (ref "U6") (pin "31") (pinfunction "PWDN_31") (pintype "passive"))
    )
  )
)
